# V7B_TI.net
KiCad netlist of a schematic drawn in EAGLE
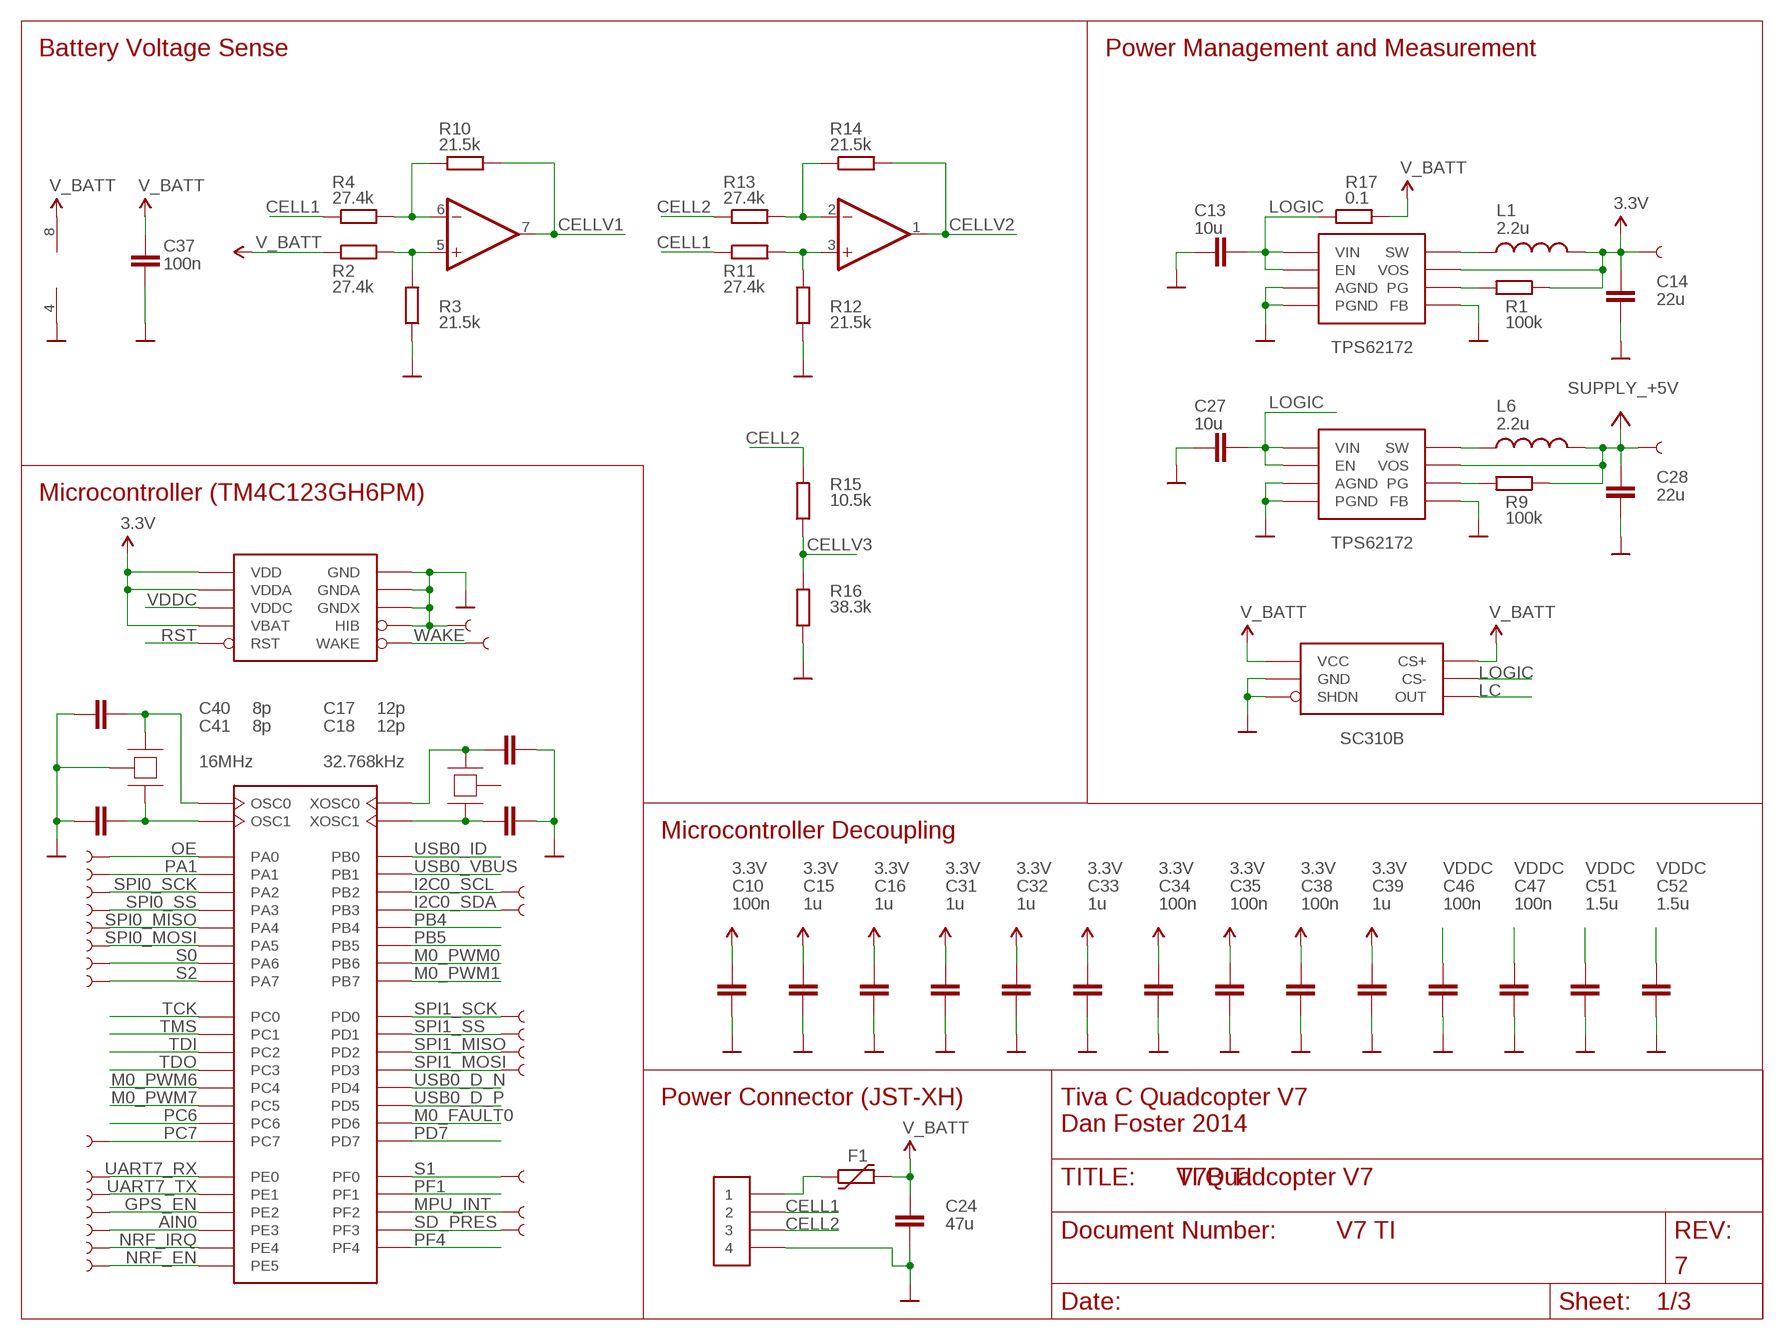
[diagram p0: schematic, sheet 1]
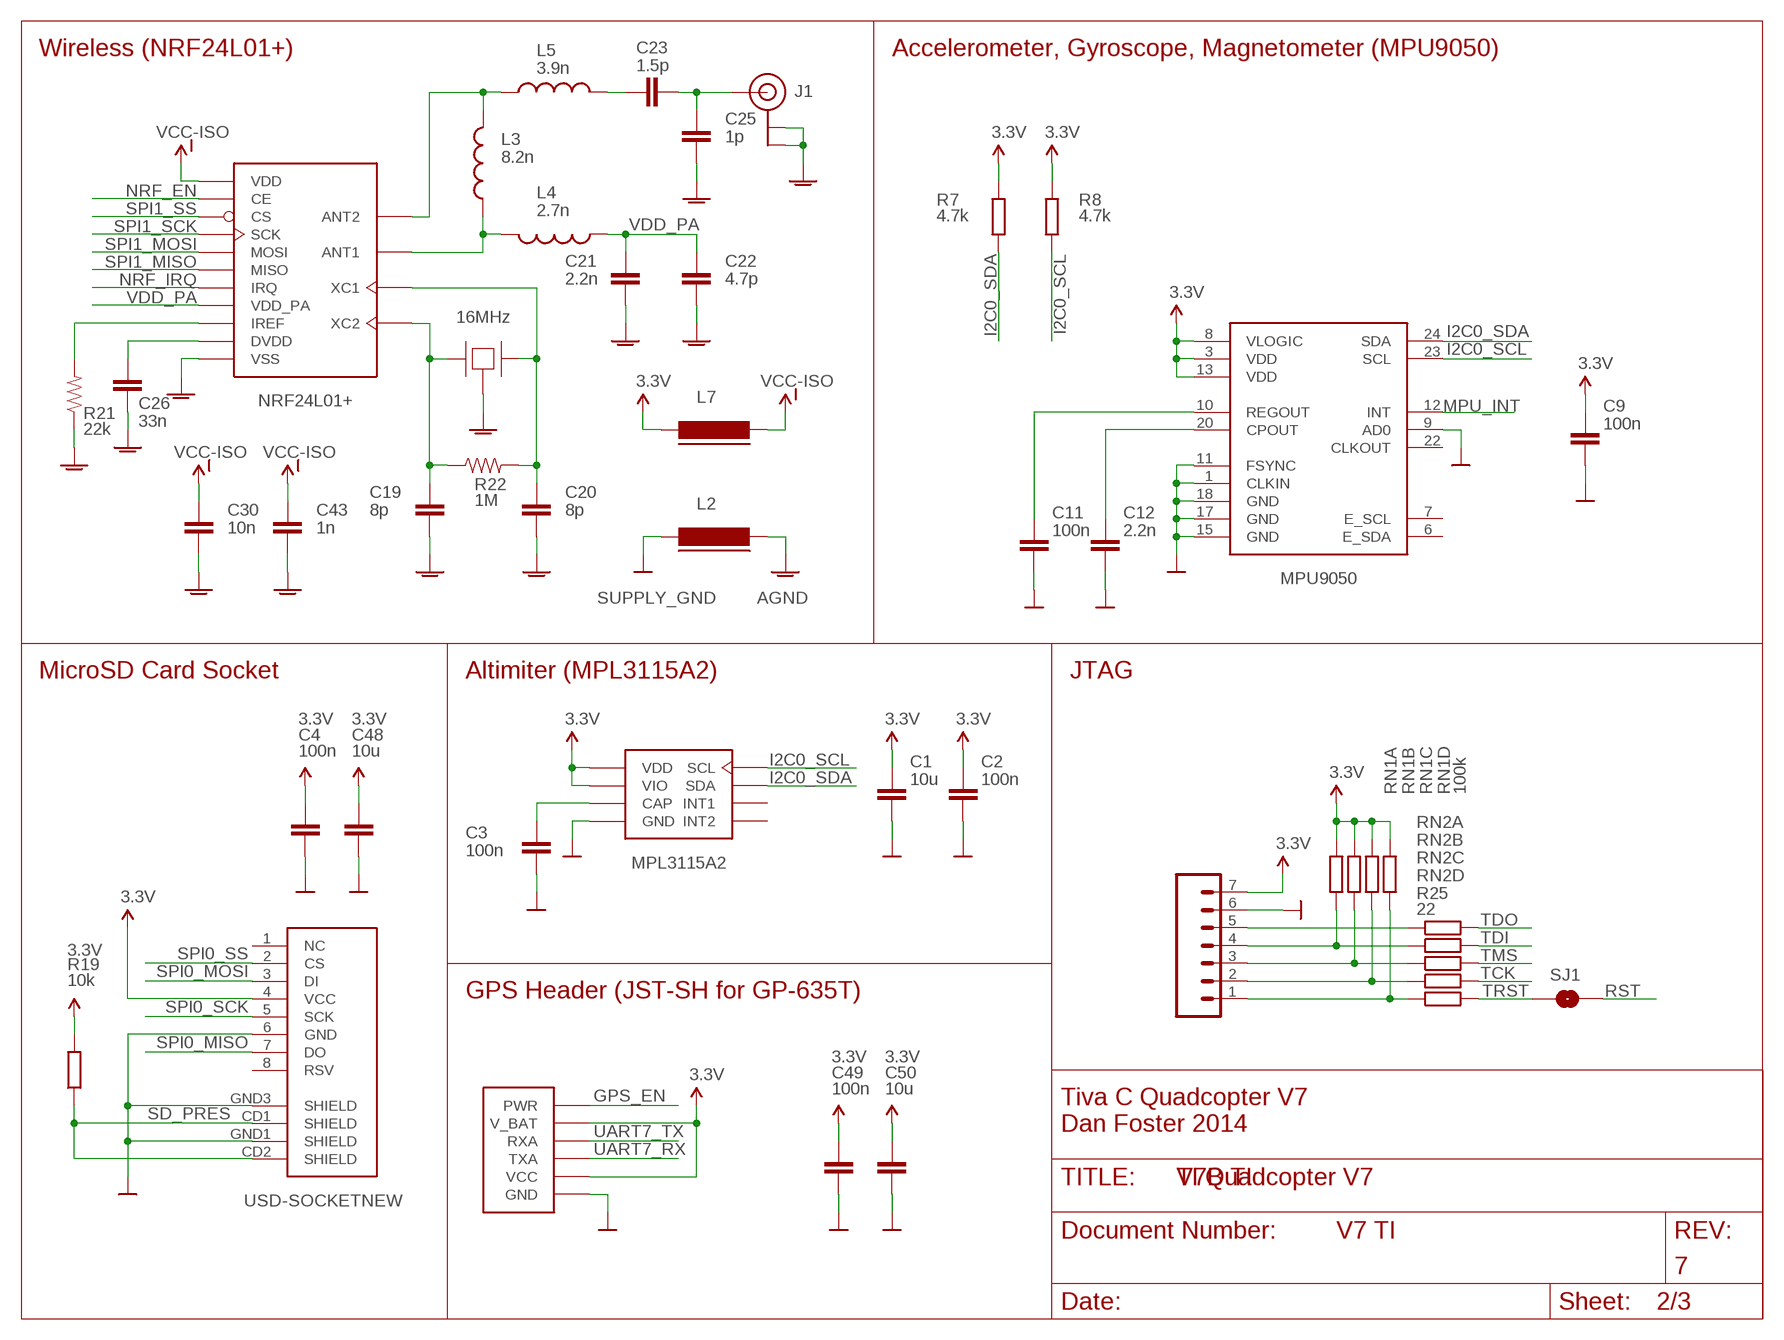
[diagram p1: schematic, sheet 2]
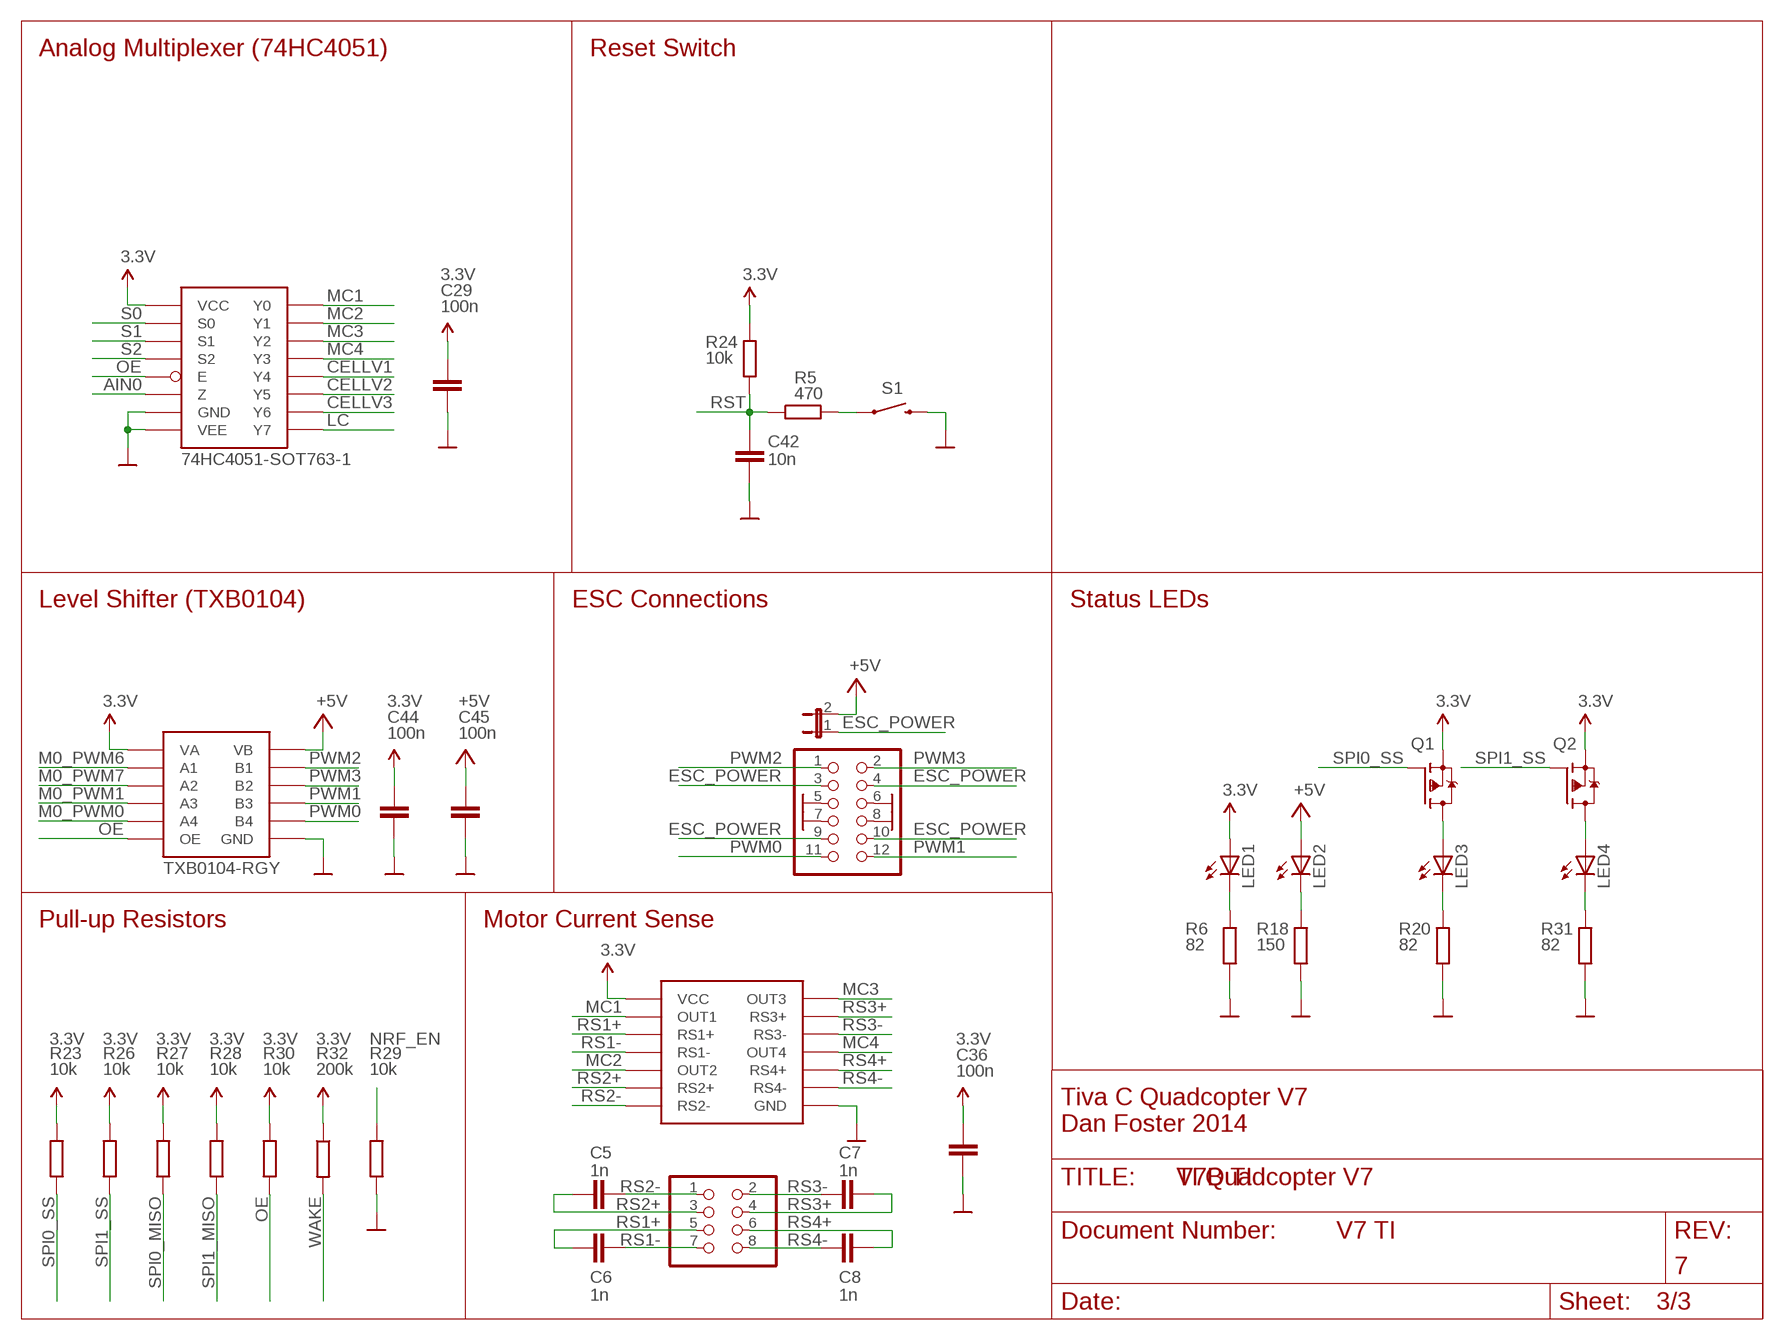
[diagram p2: schematic, sheet 3]

(export (version "E")
  (design (tool "Eeschema 10.0.6"))
  (components
    (comp (ref "C5")
      (value "1n")
      (footprint "eagle-import:C402")
      (libsource (lib "eagle-import") (part "CAPACITOR_NPOL-0402"))
    )
    (comp (ref "C6")
      (value "1n")
      (footprint "eagle-import:C402")
      (libsource (lib "eagle-import") (part "CAPACITOR_NPOL-0402"))
    )
    (comp (ref "C7")
      (value "1n")
      (footprint "eagle-import:C402")
      (libsource (lib "eagle-import") (part "CAPACITOR_NPOL-0402"))
    )
    (comp (ref "C8")
      (value "1n")
      (footprint "eagle-import:C402")
      (libsource (lib "eagle-import") (part "CAPACITOR_NPOL-0402"))
    )
    (comp (ref "C29")
      (value "100n")
      (footprint "eagle-import:C402")
      (libsource (lib "eagle-import") (part "CAPACITOR_NPOL-0402"))
    )
    (comp (ref "C36")
      (value "100n")
      (footprint "eagle-import:C402")
      (libsource (lib "eagle-import") (part "CAPACITOR_NPOL-0402"))
    )
    (comp (ref "C42")
      (value "10n")
      (footprint "eagle-import:C402")
      (libsource (lib "eagle-import") (part "CAPACITOR_NPOL-0402"))
    )
    (comp (ref "C44")
      (value "100n")
      (footprint "eagle-import:C402")
      (libsource (lib "eagle-import") (part "CAPACITOR_NPOL-0402"))
    )
    (comp (ref "C45")
      (value "100n")
      (footprint "eagle-import:C402")
      (libsource (lib "eagle-import") (part "CAPACITOR_NPOL-0402"))
    )
    (comp (ref "JP1")
      (value "PINHD-2X6")
      (footprint "eagle-import:2X06")
      (libsource (lib "eagle-import") (part "PINHD-2X6"))
    )
    (comp (ref "JP2")
      (value "PINHD-2X4")
      (footprint "eagle-import:2X04")
      (libsource (lib "eagle-import") (part "PINHD-2X4"))
    )
    (comp (ref "JP3")
      (value "JUMPER-2SMD-NO")
      (footprint "eagle-import:SJ_2S-NO")
      (libsource (lib "eagle-import") (part "JUMPER-2SMD-NO"))
    )
    (comp (ref "LED1")
      (value "LED-0603")
      (footprint "eagle-import:LED-603")
      (libsource (lib "eagle-import") (part "LED-0603"))
    )
    (comp (ref "LED2")
      (value "LED-0603")
      (footprint "eagle-import:LED-603")
      (libsource (lib "eagle-import") (part "LED-0603"))
    )
    (comp (ref "LED3")
      (value "LED-0603")
      (footprint "eagle-import:LED-603")
      (libsource (lib "eagle-import") (part "LED-0603"))
    )
    (comp (ref "LED4")
      (value "LED-0603")
      (footprint "eagle-import:LED-603")
      (libsource (lib "eagle-import") (part "LED-0603"))
    )
    (comp (ref "Q1")
      (value "BSS84CT-ND")
      (footprint "eagle-import:SOT-23")
      (libsource (lib "eagle-import") (part "TRANSISTOR_FET_TSM2301CX"))
    )
    (comp (ref "Q2")
      (value "BSS84CT-ND")
      (footprint "eagle-import:SOT-23")
      (libsource (lib "eagle-import") (part "TRANSISTOR_FET_TSM2301CX"))
    )
    (comp (ref "R5")
      (value "470")
      (footprint "eagle-import:R402")
      (libsource (lib "eagle-import") (part "RESISTOR-0402"))
    )
    (comp (ref "R6")
      (value "82")
      (footprint "eagle-import:R603")
      (libsource (lib "eagle-import") (part "RESISTOR-0603"))
    )
    (comp (ref "R18")
      (value "150")
      (footprint "eagle-import:R603")
      (libsource (lib "eagle-import") (part "RESISTOR-0603"))
    )
    (comp (ref "R20")
      (value "82")
      (footprint "eagle-import:R603")
      (libsource (lib "eagle-import") (part "RESISTOR-0603"))
    )
    (comp (ref "R23")
      (value "10k")
      (footprint "eagle-import:R402")
      (libsource (lib "eagle-import") (part "RESISTOR-0402"))
    )
    (comp (ref "R24")
      (value "10k")
      (footprint "eagle-import:R402")
      (libsource (lib "eagle-import") (part "RESISTOR-0402"))
    )
    (comp (ref "R26")
      (value "10k")
      (footprint "eagle-import:R402")
      (libsource (lib "eagle-import") (part "RESISTOR-0402"))
    )
    (comp (ref "R27")
      (value "10k")
      (footprint "eagle-import:R402")
      (libsource (lib "eagle-import") (part "RESISTOR-0402"))
    )
    (comp (ref "R28")
      (value "10k")
      (footprint "eagle-import:R402")
      (libsource (lib "eagle-import") (part "RESISTOR-0402"))
    )
    (comp (ref "R29")
      (value "10k")
      (footprint "eagle-import:R402")
      (libsource (lib "eagle-import") (part "RESISTOR-0402"))
    )
    (comp (ref "R30")
      (value "10k")
      (footprint "eagle-import:R402")
      (libsource (lib "eagle-import") (part "RESISTOR-0402"))
    )
    (comp (ref "R31")
      (value "82")
      (footprint "eagle-import:R603")
      (libsource (lib "eagle-import") (part "RESISTOR-0603"))
    )
    (comp (ref "R32")
      (value "200k")
      (footprint "eagle-import:R402")
      (libsource (lib "eagle-import") (part "RESISTOR-0402"))
    )
    (comp (ref "S1")
      (value "SWITCH-MOMENTARY-2SMD")
      (footprint "eagle-import:TACTILE_SWITCH_SMD")
      (libsource (lib "eagle-import") (part "SWITCH-MOMENTARY-2SMD"))
    )
    (comp (ref "U$1")
      (value "MAX4378XAUD+")
      (footprint "eagle-import:TSSOP-14")
      (libsource (lib "eagle-import") (part "MAX4378XAUD+"))
    )
    (comp (ref "U$8")
      (value "74HC4051")
      (footprint "eagle-import:NXP-SOT763-1")
      (libsource (lib "eagle-import") (part "74HC4051"))
    )
    (comp (ref "U$18")
      (value "TXB0104-RGY")
      (footprint "eagle-import:TI-RGY")
      (libsource (lib "eagle-import") (part "TXB0104-RGY"))
    )
    (comp (ref "C1")
      (value "10u")
      (footprint "eagle-import:C603")
      (libsource (lib "eagle-import") (part "CAPACITOR_NPOL-0603"))
    )
    (comp (ref "C2")
      (value "100n")
      (footprint "eagle-import:C402")
      (libsource (lib "eagle-import") (part "CAPACITOR_NPOL-0402"))
    )
    (comp (ref "C3")
      (value "100n")
      (footprint "eagle-import:C402")
      (libsource (lib "eagle-import") (part "CAPACITOR_NPOL-0402"))
    )
    (comp (ref "C4")
      (value "100n")
      (footprint "eagle-import:C402")
      (libsource (lib "eagle-import") (part "CAPACITOR_NPOL-0402"))
    )
    (comp (ref "C9")
      (value "100n")
      (footprint "eagle-import:C402")
      (libsource (lib "eagle-import") (part "CAPACITOR_NPOL-0402"))
    )
    (comp (ref "C11")
      (value "100n")
      (footprint "eagle-import:C402")
      (libsource (lib "eagle-import") (part "CAPACITOR_NPOL-0402"))
    )
    (comp (ref "C12")
      (value "2.2n")
      (footprint "eagle-import:C402")
      (libsource (lib "eagle-import") (part "CAPACITOR_NPOL-0402"))
    )
    (comp (ref "C19")
      (value "8p")
      (footprint "eagle-import:0402-CAP")
      (libsource (lib "eagle-import") (part "CAP0402-CAP"))
    )
    (comp (ref "C20")
      (value "8p")
      (footprint "eagle-import:0402-CAP")
      (libsource (lib "eagle-import") (part "CAP0402-CAP"))
    )
    (comp (ref "C21")
      (value "2.2n")
      (footprint "eagle-import:0402-CAP")
      (libsource (lib "eagle-import") (part "CAP0402-CAP"))
    )
    (comp (ref "C22")
      (value "4.7p")
      (footprint "eagle-import:0402-CAP")
      (libsource (lib "eagle-import") (part "CAP0402-CAP"))
    )
    (comp (ref "C23")
      (value "1.5p")
      (footprint "eagle-import:0402-CAP")
      (libsource (lib "eagle-import") (part "CAP0402-CAP"))
    )
    (comp (ref "C25")
      (value "1p")
      (footprint "eagle-import:0402-CAP")
      (libsource (lib "eagle-import") (part "CAP0402-CAP"))
    )
    (comp (ref "C26")
      (value "33n")
      (footprint "eagle-import:0402-CAP")
      (libsource (lib "eagle-import") (part "CAP0402-CAP"))
    )
    (comp (ref "C30")
      (value "10n")
      (footprint "eagle-import:0402-CAP")
      (libsource (lib "eagle-import") (part "CAP0402-CAP"))
    )
    (comp (ref "C43")
      (value "1n")
      (footprint "eagle-import:0402-CAP")
      (libsource (lib "eagle-import") (part "CAP0402-CAP"))
    )
    (comp (ref "C48")
      (value "10u")
      (footprint "eagle-import:C603")
      (libsource (lib "eagle-import") (part "CAPACITOR_NPOL-0603"))
    )
    (comp (ref "C49")
      (value "100n")
      (footprint "eagle-import:C402")
      (libsource (lib "eagle-import") (part "CAPACITOR_NPOL-0402"))
    )
    (comp (ref "C50")
      (value "10u")
      (footprint "eagle-import:C603")
      (libsource (lib "eagle-import") (part "CAPACITOR_NPOL-0603"))
    )
    (comp (ref "J1")
      (value "U.FL")
      (footprint "eagle-import:U.FL")
      (libsource (lib "eagle-import") (part "U.FL"))
    )
    (comp (ref "JP5")
      (value "M07")
      (footprint "eagle-import:1X07")
      (libsource (lib "eagle-import") (part "M07"))
    )
    (comp (ref "L2")
      (value "445-8677-1-ND")
      (footprint "eagle-import:FB603")
      (libsource (lib "eagle-import") (part "FERRITE-0603"))
    )
    (comp (ref "L3")
      (value "8.2n")
      (footprint "eagle-import:C0402")
      (libsource (lib "eagle-import") (part "INDUCTOR0402"))
    )
    (comp (ref "L4")
      (value "2.7n")
      (footprint "eagle-import:C0402")
      (libsource (lib "eagle-import") (part "INDUCTOR0402"))
    )
    (comp (ref "L5")
      (value "3.9n")
      (footprint "eagle-import:C0402")
      (libsource (lib "eagle-import") (part "INDUCTOR0402"))
    )
    (comp (ref "L7")
      (value "445-8677-1-ND")
      (footprint "eagle-import:FB603")
      (libsource (lib "eagle-import") (part "FERRITE-0603"))
    )
    (comp (ref "R7")
      (value "4.7k")
      (footprint "eagle-import:R402")
      (libsource (lib "eagle-import") (part "RESISTOR-0402"))
    )
    (comp (ref "R8")
      (value "4.7k")
      (footprint "eagle-import:R402")
      (libsource (lib "eagle-import") (part "RESISTOR-0402"))
    )
    (comp (ref "R19")
      (value "10k")
      (footprint "eagle-import:R402")
      (libsource (lib "eagle-import") (part "RESISTOR-0402"))
    )
    (comp (ref "R21")
      (value "22k")
      (footprint "eagle-import:0402-RES")
      (libsource (lib "eagle-import") (part "RESISTOR0402-RES"))
    )
    (comp (ref "R22")
      (value "1M")
      (footprint "eagle-import:0402-RES")
      (libsource (lib "eagle-import") (part "RESISTOR0402-RES"))
    )
    (comp (ref "R25")
      (value "22")
      (footprint "eagle-import:R402")
      (libsource (lib "eagle-import") (part "RESISTOR-0402"))
    )
    (comp (ref "RN1")
      (value "100k")
      (footprint "eagle-import:RN8P-4R-CRA06S")
      (libsource (lib "eagle-import") (part "RESISTOR_ARRAY_4"))
    )
    (comp (ref "RN2")
      (value "22")
      (footprint "eagle-import:RN8P-4R-CRA06S")
      (libsource (lib "eagle-import") (part "RESISTOR_ARRAY_4"))
    )
    (comp (ref "SJ1")
      (value "SOLDERJUMPERNO")
      (footprint "eagle-import:SJ_2S-NO")
      (libsource (lib "eagle-import") (part "SOLDERJUMPERNO"))
    )
    (comp (ref "U$3")
      (value "MPL3115A2")
      (footprint "eagle-import:MPLXXXXAX")
      (libsource (lib "eagle-import") (part "MPL3115A2"))
    )
    (comp (ref "U$10")
      (value "GPS-GP-635T-VERT")
      (footprint "eagle-import:JST-SH-6-SMD-T")
      (libsource (lib "eagle-import") (part "GPS-GP-635T-VERT"))
    )
    (comp (ref "U$11")
      (value "NRF24L01+")
      (footprint "eagle-import:QFN-20-4X4-0.5")
      (libsource (lib "eagle-import") (part "NRF24L01+"))
    )
    (comp (ref "U$13")
      (value "CRYSTAL-3.2X2.5")
      (footprint "eagle-import:TSX-3225")
      (libsource (lib "eagle-import") (part "CRYSTAL-3.2X2.5"))
    )
    (comp (ref "U1")
      (value "MPU9050")
      (footprint "eagle-import:QFN-24-NP")
      (libsource (lib "eagle-import") (part "MPU-9150QFN-24-NP"))
    )
    (comp (ref "U2")
      (value "USD-SOCKETNEW")
      (footprint "eagle-import:MICRO-SD-SOCKET-PP")
      (libsource (lib "eagle-import") (part "USD-SOCKETNEW"))
    )
    (comp (ref "C10")
      (value "100n")
      (footprint "eagle-import:C402")
      (libsource (lib "eagle-import") (part "CAPACITOR_NPOL-0402"))
    )
    (comp (ref "C13")
      (value "10u")
      (footprint "eagle-import:C805")
      (libsource (lib "eagle-import") (part "CAPACITOR_NPOL-0805"))
    )
    (comp (ref "C14")
      (value "22u")
      (footprint "eagle-import:C805")
      (libsource (lib "eagle-import") (part "CAPACITOR_NPOL-0805"))
    )
    (comp (ref "C15")
      (value "1u")
      (footprint "eagle-import:C402")
      (libsource (lib "eagle-import") (part "CAPACITOR_NPOL-0402"))
    )
    (comp (ref "C16")
      (value "1u")
      (footprint "eagle-import:C402")
      (libsource (lib "eagle-import") (part "CAPACITOR_NPOL-0402"))
    )
    (comp (ref "C17")
      (value "12p")
      (footprint "eagle-import:C402")
      (libsource (lib "eagle-import") (part "CAPACITOR_NPOL-0402"))
    )
    (comp (ref "C18")
      (value "12p")
      (footprint "eagle-import:C402")
      (libsource (lib "eagle-import") (part "CAPACITOR_NPOL-0402"))
    )
    (comp (ref "C24")
      (value "47u")
      (footprint "eagle-import:C1206")
      (libsource (lib "eagle-import") (part "CAPACITOR_NPOL-1206"))
    )
    (comp (ref "C27")
      (value "10u")
      (footprint "eagle-import:C805")
      (libsource (lib "eagle-import") (part "CAPACITOR_NPOL-0805"))
    )
    (comp (ref "C28")
      (value "22u")
      (footprint "eagle-import:C805")
      (libsource (lib "eagle-import") (part "CAPACITOR_NPOL-0805"))
    )
    (comp (ref "C31")
      (value "1u")
      (footprint "eagle-import:C402")
      (libsource (lib "eagle-import") (part "CAPACITOR_NPOL-0402"))
    )
    (comp (ref "C32")
      (value "1u")
      (footprint "eagle-import:C402")
      (libsource (lib "eagle-import") (part "CAPACITOR_NPOL-0402"))
    )
    (comp (ref "C33")
      (value "1u")
      (footprint "eagle-import:C402")
      (libsource (lib "eagle-import") (part "CAPACITOR_NPOL-0402"))
    )
    (comp (ref "C34")
      (value "100n")
      (footprint "eagle-import:C402")
      (libsource (lib "eagle-import") (part "CAPACITOR_NPOL-0402"))
    )
    (comp (ref "C35")
      (value "100n")
      (footprint "eagle-import:C402")
      (libsource (lib "eagle-import") (part "CAPACITOR_NPOL-0402"))
    )
    (comp (ref "C37")
      (value "100n")
      (footprint "eagle-import:C402")
      (libsource (lib "eagle-import") (part "CAPACITOR_NPOL-0402"))
    )
    (comp (ref "C38")
      (value "100n")
      (footprint "eagle-import:C402")
      (libsource (lib "eagle-import") (part "CAPACITOR_NPOL-0402"))
    )
    (comp (ref "C39")
      (value "1u")
      (footprint "eagle-import:C402")
      (libsource (lib "eagle-import") (part "CAPACITOR_NPOL-0402"))
    )
    (comp (ref "C40")
      (value "8p")
      (footprint "eagle-import:C402")
      (libsource (lib "eagle-import") (part "CAPACITOR_NPOL-0402"))
    )
    (comp (ref "C41")
      (value "8p")
      (footprint "eagle-import:C402")
      (libsource (lib "eagle-import") (part "CAPACITOR_NPOL-0402"))
    )
    (comp (ref "C46")
      (value "100n")
      (footprint "eagle-import:C402")
      (libsource (lib "eagle-import") (part "CAPACITOR_NPOL-0402"))
    )
    (comp (ref "C47")
      (value "100n")
      (footprint "eagle-import:C402")
      (libsource (lib "eagle-import") (part "CAPACITOR_NPOL-0402"))
    )
    (comp (ref "C51")
      (value "1.5u")
      (footprint "eagle-import:C402")
      (libsource (lib "eagle-import") (part "CAPACITOR_NPOL-0402"))
    )
    (comp (ref "C52")
      (value "1.5u")
      (footprint "eagle-import:C402")
      (libsource (lib "eagle-import") (part "CAPACITOR_NPOL-0402"))
    )
    (comp (ref "F1")
      (value "FUSE_PTC-1812")
      (footprint "eagle-import:PTC1812L")
      (libsource (lib "eagle-import") (part "FUSE_PTC-1812"))
    )
    (comp (ref "IC2")
      (value "OPA2743EA")
      (footprint "eagle-import:MSOP08")
      (libsource (lib "eagle-import") (part "OPA2743EA"))
    )
    (comp (ref "L1")
      (value "2.2u")
      (footprint "eagle-import:1210")
      (libsource (lib "eagle-import") (part "INDUCTOR1210"))
    )
    (comp (ref "L6")
      (value "2.2u")
      (footprint "eagle-import:1210")
      (libsource (lib "eagle-import") (part "INDUCTOR1210"))
    )
    (comp (ref "R1")
      (value "100k")
      (footprint "eagle-import:R402")
      (libsource (lib "eagle-import") (part "RESISTOR-0402"))
    )
    (comp (ref "R2")
      (value "27.4k")
      (footprint "eagle-import:R402")
      (libsource (lib "eagle-import") (part "RESISTOR-0402"))
    )
    (comp (ref "R3")
      (value "21.5k")
      (footprint "eagle-import:R402")
      (libsource (lib "eagle-import") (part "RESISTOR-0402"))
    )
    (comp (ref "R4")
      (value "27.4k")
      (footprint "eagle-import:R402")
      (libsource (lib "eagle-import") (part "RESISTOR-0402"))
    )
    (comp (ref "R9")
      (value "100k")
      (footprint "eagle-import:R402")
      (libsource (lib "eagle-import") (part "RESISTOR-0402"))
    )
    (comp (ref "R10")
      (value "21.5k")
      (footprint "eagle-import:R402")
      (libsource (lib "eagle-import") (part "RESISTOR-0402"))
    )
    (comp (ref "R11")
      (value "27.4k")
      (footprint "eagle-import:R402")
      (libsource (lib "eagle-import") (part "RESISTOR-0402"))
    )
    (comp (ref "R12")
      (value "21.5k")
      (footprint "eagle-import:R402")
      (libsource (lib "eagle-import") (part "RESISTOR-0402"))
    )
    (comp (ref "R13")
      (value "27.4k")
      (footprint "eagle-import:R402")
      (libsource (lib "eagle-import") (part "RESISTOR-0402"))
    )
    (comp (ref "R14")
      (value "21.5k")
      (footprint "eagle-import:R402")
      (libsource (lib "eagle-import") (part "RESISTOR-0402"))
    )
    (comp (ref "R15")
      (value "10.5k")
      (footprint "eagle-import:R402")
      (libsource (lib "eagle-import") (part "RESISTOR-0402"))
    )
    (comp (ref "R16")
      (value "38.3k")
      (footprint "eagle-import:R402")
      (libsource (lib "eagle-import") (part "RESISTOR-0402"))
    )
    (comp (ref "R17")
      (value "0.1")
      (footprint "eagle-import:R1206")
      (libsource (lib "eagle-import") (part "RESISTOR-1206"))
    )
    (comp (ref "TP1")
      (value "TEST-POINT3")
      (footprint "eagle-import:PAD.03X.03")
      (libsource (lib "eagle-import") (part "TEST-POINT3"))
    )
    (comp (ref "TP2")
      (value "TEST-POINT3")
      (footprint "eagle-import:PAD.03X.03")
      (libsource (lib "eagle-import") (part "TEST-POINT3"))
    )
    (comp (ref "TP3")
      (value "TEST-POINT3")
      (footprint "eagle-import:PAD.03X.03")
      (libsource (lib "eagle-import") (part "TEST-POINT3"))
    )
    (comp (ref "TP4")
      (value "TEST-POINT3")
      (footprint "eagle-import:PAD.03X.03")
      (libsource (lib "eagle-import") (part "TEST-POINT3"))
    )
    (comp (ref "TP5")
      (value "TEST-POINT3")
      (footprint "eagle-import:PAD.03X.03")
      (libsource (lib "eagle-import") (part "TEST-POINT3"))
    )
    (comp (ref "TP6")
      (value "TEST-POINT3")
      (footprint "eagle-import:PAD.03X.03")
      (libsource (lib "eagle-import") (part "TEST-POINT3"))
    )
    (comp (ref "TP7")
      (value "TEST-POINT3")
      (footprint "eagle-import:PAD.03X.03")
      (libsource (lib "eagle-import") (part "TEST-POINT3"))
    )
    (comp (ref "TP8")
      (value "TEST-POINT3")
      (footprint "eagle-import:PAD.03X.03")
      (libsource (lib "eagle-import") (part "TEST-POINT3"))
    )
    (comp (ref "TP9")
      (value "TEST-POINT3")
      (footprint "eagle-import:PAD.03X.03")
      (libsource (lib "eagle-import") (part "TEST-POINT3"))
    )
    (comp (ref "TP10")
      (value "TEST-POINT3")
      (footprint "eagle-import:PAD.03X.03")
      (libsource (lib "eagle-import") (part "TEST-POINT3"))
    )
    (comp (ref "TP11")
      (value "TEST-POINT3")
      (footprint "eagle-import:PAD.03X.03")
      (libsource (lib "eagle-import") (part "TEST-POINT3"))
    )
    (comp (ref "TP12")
      (value "TEST-POINT3")
      (footprint "eagle-import:PAD.03X.03")
      (libsource (lib "eagle-import") (part "TEST-POINT3"))
    )
    (comp (ref "TP13")
      (value "TEST-POINT3")
      (footprint "eagle-import:PAD.03X.03")
      (libsource (lib "eagle-import") (part "TEST-POINT3"))
    )
    (comp (ref "TP14")
      (value "TEST-POINT3")
      (footprint "eagle-import:PAD.03X.03")
      (libsource (lib "eagle-import") (part "TEST-POINT3"))
    )
    (comp (ref "TP15")
      (value "TEST-POINT3")
      (footprint "eagle-import:PAD.03X.03")
      (libsource (lib "eagle-import") (part "TEST-POINT3"))
    )
    (comp (ref "TP16")
      (value "TEST-POINT3")
      (footprint "eagle-import:PAD.03X.03")
      (libsource (lib "eagle-import") (part "TEST-POINT3"))
    )
    (comp (ref "TP17")
      (value "TEST-POINT3")
      (footprint "eagle-import:PAD.03X.03")
      (libsource (lib "eagle-import") (part "TEST-POINT3"))
    )
    (comp (ref "TP18")
      (value "TEST-POINT3")
      (footprint "eagle-import:PAD.03X.03")
      (libsource (lib "eagle-import") (part "TEST-POINT3"))
    )
    (comp (ref "TP19")
      (value "TEST-POINT3")
      (footprint "eagle-import:PAD.03X.03")
      (libsource (lib "eagle-import") (part "TEST-POINT3"))
    )
    (comp (ref "TP20")
      (value "TEST-POINT3")
      (footprint "eagle-import:PAD.03X.03")
      (libsource (lib "eagle-import") (part "TEST-POINT3"))
    )
    (comp (ref "TP21")
      (value "TEST-POINT3")
      (footprint "eagle-import:PAD.03X.03")
      (libsource (lib "eagle-import") (part "TEST-POINT3"))
    )
    (comp (ref "TP22")
      (value "TEST-POINT3")
      (footprint "eagle-import:PAD.03X.03")
      (libsource (lib "eagle-import") (part "TEST-POINT3"))
    )
    (comp (ref "TP23")
      (value "TEST-POINT3")
      (footprint "eagle-import:PAD.03X.03")
      (libsource (lib "eagle-import") (part "TEST-POINT3"))
    )
    (comp (ref "TP24")
      (value "TEST-POINT3")
      (footprint "eagle-import:PAD.03X.03")
      (libsource (lib "eagle-import") (part "TEST-POINT3"))
    )
    (comp (ref "TP25")
      (value "TEST-POINT3")
      (footprint "eagle-import:PAD.03X.03")
      (libsource (lib "eagle-import") (part "TEST-POINT3"))
    )
    (comp (ref "TP26")
      (value "TEST-POINT3")
      (footprint "eagle-import:PAD.03X.03")
      (libsource (lib "eagle-import") (part "TEST-POINT3"))
    )
    (comp (ref "TP27")
      (value "TEST-POINT3")
      (footprint "eagle-import:PAD.03X.03")
      (libsource (lib "eagle-import") (part "TEST-POINT3"))
    )
    (comp (ref "TP29")
      (value "TEST-POINT3")
      (footprint "eagle-import:PAD.03X.03")
      (libsource (lib "eagle-import") (part "TEST-POINT3"))
    )
    (comp (ref "U$2")
      (value "TPS62172")
      (footprint "eagle-import:S-PWSON-N8")
      (libsource (lib "eagle-import") (part "TPS62172"))
    )
    (comp (ref "U$4")
      (value "TPS62172")
      (footprint "eagle-import:S-PWSON-N8")
      (libsource (lib "eagle-import") (part "TPS62172"))
    )
    (comp (ref "U$5")
      (value "TM4C123GH6PM")
      (footprint "eagle-import:TI-PM")
      (libsource (lib "eagle-import") (part "TM4C123GH6PM"))
    )
    (comp (ref "U$6")
      (value "JST-XH-4-SMD")
      (footprint "eagle-import:JST-XH-4-SMD")
      (libsource (lib "eagle-import") (part "JST-XH-4-SMD"))
    )
    (comp (ref "U$7")
      (value "CRYSTAL-3.2X2.5")
      (footprint "eagle-import:TSX-3225")
      (libsource (lib "eagle-import") (part "CRYSTAL-3.2X2.5"))
    )
    (comp (ref "U$9")
      (value "SC130")
      (footprint "eagle-import:SOT-23-6")
      (libsource (lib "eagle-import") (part "SC130"))
    )
    (comp (ref "U$12")
      (value "CRYSTAL-WATCH-SMD")
      (footprint "eagle-import:CRYSTAL-WATCH-SMD")
      (libsource (lib "eagle-import") (part "CRYSTAL-WATCH-SMD"))
    )
  )
  (nets
    (net (code "1") (name "+5V") (class "Default")
      (node (ref "C28") (pin "2") (pinfunction "2_2") (pintype "passive"))
      (node (ref "C45") (pin "1") (pinfunction "1_1") (pintype "passive"))
      (node (ref "JP3") (pin "2") (pinfunction "2_2") (pintype "passive"))
      (node (ref "L6") (pin "2") (pinfunction "2_2") (pintype "passive"))
      (node (ref "LED2") (pin "A") (pinfunction "A_A") (pintype "passive"))
      (node (ref "R9") (pin "1") (pinfunction "1_1") (pintype "passive"))
      (node (ref "TP14") (pin "P$1") (pinfunction "1_P$1") (pintype "bidirectional"))
      (node (ref "U$18") (pin "14") (pinfunction "VB_14") (pintype "power_in"))
      (node (ref "U$4") (pin "6") (pinfunction "VOS_6") (pintype "input"))
    )
    (net (code "2") (name "3.3V") (class "Default")
      (node (ref "C1") (pin "1") (pinfunction "1_1") (pintype "passive"))
      (node (ref "C10") (pin "1") (pinfunction "1_1") (pintype "passive"))
      (node (ref "C14") (pin "2") (pinfunction "2_2") (pintype "passive"))
      (node (ref "C15") (pin "1") (pinfunction "1_1") (pintype "passive"))
      (node (ref "C16") (pin "1") (pinfunction "1_1") (pintype "passive"))
      (node (ref "C2") (pin "1") (pinfunction "1_1") (pintype "passive"))
      (node (ref "C29") (pin "1") (pinfunction "1_1") (pintype "passive"))
      (node (ref "C31") (pin "1") (pinfunction "1_1") (pintype "passive"))
      (node (ref "C32") (pin "1") (pinfunction "1_1") (pintype "passive"))
      (node (ref "C33") (pin "1") (pinfunction "1_1") (pintype "passive"))
      (node (ref "C34") (pin "1") (pinfunction "1_1") (pintype "passive"))
      (node (ref "C35") (pin "1") (pinfunction "1_1") (pintype "passive"))
      (node (ref "C36") (pin "1") (pinfunction "1_1") (pintype "passive"))
      (node (ref "C38") (pin "1") (pinfunction "1_1") (pintype "passive"))
      (node (ref "C39") (pin "1") (pinfunction "1_1") (pintype "passive"))
      (node (ref "C4") (pin "1") (pinfunction "1_1") (pintype "passive"))
      (node (ref "C44") (pin "1") (pinfunction "1_1") (pintype "passive"))
      (node (ref "C48") (pin "1") (pinfunction "1_1") (pintype "passive"))
      (node (ref "C49") (pin "1") (pinfunction "1_1") (pintype "passive"))
      (node (ref "C50") (pin "1") (pinfunction "1_1") (pintype "passive"))
      (node (ref "C9") (pin "1") (pinfunction "1_1") (pintype "passive"))
      (node (ref "JP5") (pin "7") (pinfunction "7_7") (pintype "passive"))
      (node (ref "L1") (pin "2") (pinfunction "2_2") (pintype "passive"))
      (node (ref "L7") (pin "1") (pinfunction "1_1") (pintype "passive"))
      (node (ref "LED1") (pin "A") (pinfunction "A_A") (pintype "passive"))
      (node (ref "Q1") (pin "2") (pinfunction "S_2") (pintype "passive"))
      (node (ref "Q2") (pin "2") (pinfunction "S_2") (pintype "passive"))
      (node (ref "R1") (pin "1") (pinfunction "1_1") (pintype "passive"))
      (node (ref "R19") (pin "2") (pinfunction "2_2") (pintype "passive"))
      (node (ref "R23") (pin "2") (pinfunction "2_2") (pintype "passive"))
      (node (ref "R24") (pin "2") (pinfunction "2_2") (pintype "passive"))
      (node (ref "R26") (pin "2") (pinfunction "2_2") (pintype "passive"))
      (node (ref "R27") (pin "2") (pinfunction "2_2") (pintype "passive"))
      (node (ref "R28") (pin "2") (pinfunction "2_2") (pintype "passive"))
      (node (ref "R30") (pin "2") (pinfunction "2_2") (pintype "passive"))
      (node (ref "R32") (pin "1") (pinfunction "1_1") (pintype "passive"))
      (node (ref "R7") (pin "1") (pinfunction "1_1") (pintype "passive"))
      (node (ref "R8") (pin "1") (pinfunction "1_1") (pintype "passive"))
      (node (ref "RN1") (pin "5") (pinfunction "2_5") (pintype "passive"))
      (node (ref "RN1") (pin "6") (pinfunction "2_6") (pintype "passive"))
      (node (ref "RN1") (pin "7") (pinfunction "2_7") (pintype "passive"))
      (node (ref "RN1") (pin "8") (pinfunction "2_8") (pintype "passive"))
      (node (ref "TP15") (pin "P$1") (pinfunction "1_P$1") (pintype "bidirectional"))
      (node (ref "U$1") (pin "P$4") (pinfunction "VCC_P$4") (pintype "power_in"))
      (node (ref "U$10") (pin "2") (pinfunction "VCC_2") (pintype "power_in"))
      (node (ref "U$10") (pin "5") (pinfunction "V_BAT_5") (pintype "input"))
      (node (ref "U$18") (pin "1") (pinfunction "VA_1") (pintype "power_in"))
      (node (ref "U$2") (pin "6") (pinfunction "VOS_6") (pintype "input"))
      (node (ref "U$3") (pin "1") (pinfunction "VDD_1") (pintype "power_in"))
      (node (ref "U$3") (pin "4") (pinfunction "VIO_4") (pintype "power_in"))
      (node (ref "U$5") (pin "P$11") (pinfunction "VDD_P$11") (pintype "power_in"))
      (node (ref "U$5") (pin "P$2") (pinfunction "VDDA_P$2") (pintype "power_in"))
      (node (ref "U$5") (pin "P$26") (pinfunction "VDD_P$26") (pintype "power_in"))
      (node (ref "U$5") (pin "P$37") (pinfunction "VBAT_P$37") (pintype "power_in"))
      (node (ref "U$5") (pin "P$42") (pinfunction "VDD_P$42") (pintype "power_in"))
      (node (ref "U$5") (pin "P$54") (pinfunction "VDD_P$54") (pintype "power_in"))
      (node (ref "U$8") (pin "16") (pinfunction "VCC_16") (pintype "power_in"))
      (node (ref "U$8") (pin "PAD") (pinfunction "VCC_PAD") (pintype "power_in"))
      (node (ref "U1") (pin "13") (pinfunction "VDD_13") (pintype "bidirectional"))
      (node (ref "U1") (pin "3") (pinfunction "VDD_3") (pintype "bidirectional"))
      (node (ref "U1") (pin "8") (pinfunction "VLOGIC_8") (pintype "bidirectional"))
      (node (ref "U2") (pin "4") (pinfunction "VCC_4") (pintype "bidirectional"))
    )
    (net (code "3") (name "AGND") (class "Default")
      (node (ref "C19") (pin "2") (pinfunction "2_2") (pintype "passive"))
      (node (ref "C20") (pin "2") (pinfunction "2_2") (pintype "passive"))
      (node (ref "C21") (pin "2") (pinfunction "2_2") (pintype "passive"))
      (node (ref "C22") (pin "2") (pinfunction "2_2") (pintype "passive"))
      (node (ref "C25") (pin "2") (pinfunction "2_2") (pintype "passive"))
      (node (ref "C26") (pin "2") (pinfunction "2_2") (pintype "passive"))
      (node (ref "C30") (pin "2") (pinfunction "2_2") (pintype "passive"))
      (node (ref "C43") (pin "2") (pinfunction "2_2") (pintype "passive"))
      (node (ref "J1") (pin "P$1") (pinfunction "GND_P$1") (pintype "bidirectional"))
      (node (ref "J1") (pin "P$2") (pinfunction "GND_P$2") (pintype "bidirectional"))
      (node (ref "L2") (pin "2") (pinfunction "2_2") (pintype "passive"))
      (node (ref "R21") (pin "1") (pinfunction "1_1") (pintype "passive"))
      (node (ref "U$11") (pin "P$14") (pinfunction "VSS_P$14") (pintype "power_in"))
      (node (ref "U$11") (pin "P$17") (pinfunction "VSS_P$17") (pintype "power_in"))
      (node (ref "U$11") (pin "P$20") (pinfunction "VSS_P$20") (pintype "power_in"))
      (node (ref "U$11") (pin "P$8") (pinfunction "VSS_P$8") (pintype "power_in"))
      (node (ref "U$13") (pin "G1") (pinfunction "CASE_G1") (pintype "power_in"))
      (node (ref "U$13") (pin "G2") (pinfunction "CASE_G2") (pintype "power_in"))
    )
    (net (code "4") (name "AIN0") (class "Default")
      (node (ref "TP11") (pin "P$1") (pinfunction "1_P$1") (pintype "bidirectional"))
      (node (ref "U$5") (pin "P$6") (pinfunction "PE3_P$6") (pintype "bidirectional"))
      (node (ref "U$8") (pin "3") (pinfunction "Z_3") (pintype "bidirectional"))
    )
    (net (code "5") (name "CASE") (class "Default")
      (node (ref "U$12") (pin "BODY") (pinfunction "CASE_BODY") (pintype "power_in"))
    )
    (net (code "6") (name "CELL1") (class "Default")
      (node (ref "R11") (pin "1") (pinfunction "1_1") (pintype "passive"))
      (node (ref "R4") (pin "1") (pinfunction "1_1") (pintype "passive"))
      (node (ref "U$6") (pin "2") (pinfunction "2_2") (pintype "bidirectional"))
    )
    (net (code "7") (name "CELL2") (class "Default")
      (node (ref "R13") (pin "1") (pinfunction "1_1") (pintype "passive"))
      (node (ref "R15") (pin "2") (pinfunction "2_2") (pintype "passive"))
      (node (ref "U$6") (pin "3") (pinfunction "3_3") (pintype "bidirectional"))
    )
    (net (code "8") (name "CELLV1") (class "Default")
      (node (ref "IC2") (pin "7") (pinfunction "OUT_7") (pintype "output"))
      (node (ref "R10") (pin "2") (pinfunction "2_2") (pintype "passive"))
      (node (ref "U$8") (pin "1") (pinfunction "Y4_1") (pintype "bidirectional"))
    )
    (net (code "9") (name "CELLV2") (class "Default")
      (node (ref "IC2") (pin "1") (pinfunction "OUT_1") (pintype "output"))
      (node (ref "R14") (pin "2") (pinfunction "2_2") (pintype "passive"))
      (node (ref "U$8") (pin "5") (pinfunction "Y5_5") (pintype "bidirectional"))
    )
    (net (code "10") (name "CELLV3") (class "Default")
      (node (ref "R15") (pin "1") (pinfunction "1_1") (pintype "passive"))
      (node (ref "R16") (pin "2") (pinfunction "2_2") (pintype "passive"))
      (node (ref "U$8") (pin "2") (pinfunction "Y6_2") (pintype "bidirectional"))
    )
    (net (code "11") (name "ESC_POWER") (class "Default")
      (node (ref "JP1") (pin "10") (pinfunction "10_10") (pintype "passive"))
      (node (ref "JP1") (pin "3") (pinfunction "3_3") (pintype "passive"))
      (node (ref "JP1") (pin "4") (pinfunction "4_4") (pintype "passive"))
      (node (ref "JP1") (pin "9") (pinfunction "9_9") (pintype "passive"))
      (node (ref "JP3") (pin "1") (pinfunction "1_1") (pintype "passive"))
    )
    (net (code "12") (name "GND") (class "Default")
      (node (ref "C1") (pin "2") (pinfunction "2_2") (pintype "passive"))
      (node (ref "C10") (pin "2") (pinfunction "2_2") (pintype "passive"))
      (node (ref "C11") (pin "2") (pinfunction "2_2") (pintype "passive"))
      (node (ref "C12") (pin "2") (pinfunction "2_2") (pintype "passive"))
      (node (ref "C13") (pin "2") (pinfunction "2_2") (pintype "passive"))
      (node (ref "C14") (pin "1") (pinfunction "1_1") (pintype "passive"))
      (node (ref "C15") (pin "2") (pinfunction "2_2") (pintype "passive"))
      (node (ref "C16") (pin "2") (pinfunction "2_2") (pintype "passive"))
      (node (ref "C17") (pin "2") (pinfunction "2_2") (pintype "passive"))
      (node (ref "C18") (pin "2") (pinfunction "2_2") (pintype "passive"))
      (node (ref "C2") (pin "2") (pinfunction "2_2") (pintype "passive"))
      (node (ref "C24") (pin "2") (pinfunction "2_2") (pintype "passive"))
      (node (ref "C27") (pin "2") (pinfunction "2_2") (pintype "passive"))
      (node (ref "C28") (pin "1") (pinfunction "1_1") (pintype "passive"))
      (node (ref "C29") (pin "2") (pinfunction "2_2") (pintype "passive"))
      (node (ref "C3") (pin "2") (pinfunction "2_2") (pintype "passive"))
      (node (ref "C31") (pin "2") (pinfunction "2_2") (pintype "passive"))
      (node (ref "C32") (pin "2") (pinfunction "2_2") (pintype "passive"))
      (node (ref "C33") (pin "2") (pinfunction "2_2") (pintype "passive"))
      (node (ref "C34") (pin "2") (pinfunction "2_2") (pintype "passive"))
      (node (ref "C35") (pin "2") (pinfunction "2_2") (pintype "passive"))
      (node (ref "C36") (pin "2") (pinfunction "2_2") (pintype "passive"))
      (node (ref "C37") (pin "2") (pinfunction "2_2") (pintype "passive"))
      (node (ref "C38") (pin "2") (pinfunction "2_2") (pintype "passive"))
      (node (ref "C39") (pin "2") (pinfunction "2_2") (pintype "passive"))
      (node (ref "C4") (pin "2") (pinfunction "2_2") (pintype "passive"))
      (node (ref "C40") (pin "1") (pinfunction "1_1") (pintype "passive"))
      (node (ref "C41") (pin "1") (pinfunction "1_1") (pintype "passive"))
      (node (ref "C42") (pin "2") (pinfunction "2_2") (pintype "passive"))
      (node (ref "C44") (pin "2") (pinfunction "2_2") (pintype "passive"))
      (node (ref "C45") (pin "2") (pinfunction "2_2") (pintype "passive"))
      (node (ref "C46") (pin "2") (pinfunction "2_2") (pintype "passive"))
      (node (ref "C47") (pin "2") (pinfunction "2_2") (pintype "passive"))
      (node (ref "C48") (pin "2") (pinfunction "2_2") (pintype "passive"))
      (node (ref "C49") (pin "2") (pinfunction "2_2") (pintype "passive"))
      (node (ref "C50") (pin "2") (pinfunction "2_2") (pintype "passive"))
      (node (ref "C51") (pin "2") (pinfunction "2_2") (pintype "passive"))
      (node (ref "C52") (pin "2") (pinfunction "2_2") (pintype "passive"))
      (node (ref "C9") (pin "2") (pinfunction "2_2") (pintype "passive"))
      (node (ref "IC2") (pin "4") (pinfunction "V-_4") (pintype "power_in"))
      (node (ref "JP1") (pin "5") (pinfunction "5_5") (pintype "passive"))
      (node (ref "JP1") (pin "6") (pinfunction "6_6") (pintype "passive"))
      (node (ref "JP1") (pin "7") (pinfunction "7_7") (pintype "passive"))
      (node (ref "JP1") (pin "8") (pinfunction "8_8") (pintype "passive"))
      (node (ref "JP5") (pin "6") (pinfunction "6_6") (pintype "passive"))
      (node (ref "L2") (pin "1") (pinfunction "1_1") (pintype "passive"))
      (node (ref "R12") (pin "1") (pinfunction "1_1") (pintype "passive"))
      (node (ref "R16") (pin "1") (pinfunction "1_1") (pintype "passive"))
      (node (ref "R18") (pin "2") (pinfunction "2_2") (pintype "passive"))
      (node (ref "R20") (pin "2") (pinfunction "2_2") (pintype "passive"))
      (node (ref "R29") (pin "1") (pinfunction "1_1") (pintype "passive"))
      (node (ref "R3") (pin "1") (pinfunction "1_1") (pintype "passive"))
      (node (ref "R31") (pin "2") (pinfunction "2_2") (pintype "passive"))
      (node (ref "R6") (pin "2") (pinfunction "2_2") (pintype "passive"))
      (node (ref "S1") (pin "3") (pinfunction "2_3") (pintype "passive"))
      (node (ref "TP16") (pin "P$1") (pinfunction "1_P$1") (pintype "bidirectional"))
      (node (ref "U$1") (pin "P$11") (pinfunction "GND_P$11") (pintype "power_in"))
      (node (ref "U$10") (pin "1") (pinfunction "GND_1") (pintype "power_in"))
      (node (ref "U$18") (pin "7") (pinfunction "GND_7") (pintype "power_in"))
      (node (ref "U$18") (pin "PAD") (pinfunction "GND_PAD") (pintype "power_in"))
      (node (ref "U$18") (pin "V1") (pinfunction "GND_V1") (pintype "power_in"))
      (node (ref "U$18") (pin "V2") (pinfunction "GND_V2") (pintype "power_in"))
      (node (ref "U$18") (pin "V3") (pinfunction "GND_V3") (pintype "power_in"))
      (node (ref "U$18") (pin "V4") (pinfunction "GND_V4") (pintype "power_in"))
      (node (ref "U$2") (pin "1") (pinfunction "PGND_1") (pintype "power_in"))
      (node (ref "U$2") (pin "4") (pinfunction "AGND_4") (pintype "power_in"))
      (node (ref "U$2") (pin "5") (pinfunction "FB_5") (pintype "input"))
      (node (ref "U$2") (pin "PAD") (pinfunction "AGND_PAD") (pintype "power_in"))
      (node (ref "U$2") (pin "VIA1") (pinfunction "AGND_VIA1") (pintype "power_in"))
      (node (ref "U$2") (pin "VIA2") (pinfunction "AGND_VIA2") (pintype "power_in"))
      (node (ref "U$3") (pin "3") (pinfunction "GND_3") (pintype "power_in"))
      (node (ref "U$4") (pin "1") (pinfunction "PGND_1") (pintype "power_in"))
      (node (ref "U$4") (pin "4") (pinfunction "AGND_4") (pintype "power_in"))
      (node (ref "U$4") (pin "5") (pinfunction "FB_5") (pintype "input"))
      (node (ref "U$4") (pin "PAD") (pinfunction "AGND_PAD") (pintype "power_in"))
      (node (ref "U$4") (pin "VIA1") (pinfunction "AGND_VIA1") (pintype "power_in"))
      (node (ref "U$4") (pin "VIA2") (pinfunction "AGND_VIA2") (pintype "power_in"))
      (node (ref "U$5") (pin "P$12") (pinfunction "GND_P$12") (pintype "power_in"))
      (node (ref "U$5") (pin "P$27") (pinfunction "GND_P$27") (pintype "power_in"))
      (node (ref "U$5") (pin "P$3") (pinfunction "GNDA_P$3") (pintype "power_in"))
      (node (ref "U$5") (pin "P$33") (pinfunction "HIB_P$33") (pintype "input"))
      (node (ref "U$5") (pin "P$35") (pinfunction "GNDX_P$35") (pintype "power_in"))
      (node (ref "U$5") (pin "P$39") (pinfunction "GND_P$39") (pintype "power_in"))
      (node (ref "U$5") (pin "P$55") (pinfunction "GND_P$55") (pintype "power_in"))
      (node (ref "U$6") (pin "4") (pinfunction "4_4") (pintype "bidirectional"))
      (node (ref "U$7") (pin "G1") (pinfunction "CASE_G1") (pintype "power_in"))
      (node (ref "U$7") (pin "G2") (pinfunction "CASE_G2") (pintype "power_in"))
      (node (ref "U$8") (pin "7") (pinfunction "VEE_7") (pintype "power_in"))
      (node (ref "U$8") (pin "8") (pinfunction "GND_8") (pintype "power_in"))
      (node (ref "U$9") (pin "1") (pinfunction "SHDN_1") (pintype "input"))
      (node (ref "U$9") (pin "2") (pinfunction "GND_2") (pintype "power_in"))
      (node (ref "U1") (pin "1") (pinfunction "CLKIN_1") (pintype "bidirectional"))
      (node (ref "U1") (pin "11") (pinfunction "FSYNC_11") (pintype "bidirectional"))
      (node (ref "U1") (pin "15") (pinfunction "GND_15") (pintype "bidirectional"))
      (node (ref "U1") (pin "17") (pinfunction "GND_17") (pintype "bidirectional"))
      (node (ref "U1") (pin "18") (pinfunction "GND_18") (pintype "bidirectional"))
      (node (ref "U1") (pin "9") (pinfunction "AD0_9") (pintype "bidirectional"))
      (node (ref "U2") (pin "6") (pinfunction "GND_6") (pintype "bidirectional"))
      (node (ref "U2") (pin "GND1") (pinfunction "SHIELD_GND1") (pintype "bidirectional"))
      (node (ref "U2") (pin "GND3") (pinfunction "SHIELD_GND3") (pintype "bidirectional"))
    )
    (net (code "13") (name "GPS_EN") (class "Default")
      (node (ref "TP21") (pin "P$1") (pinfunction "1_P$1") (pintype "bidirectional"))
      (node (ref "U$10") (pin "6") (pinfunction "PWR_6") (pintype "input"))
      (node (ref "U$5") (pin "P$7") (pinfunction "PE2_P$7") (pintype "bidirectional"))
    )
    (net (code "14") (name "I2C0_SCL") (class "Default")
      (node (ref "R8") (pin "2") (pinfunction "2_2") (pintype "passive"))
      (node (ref "TP5") (pin "P$1") (pinfunction "1_P$1") (pintype "bidirectional"))
      (node (ref "U$3") (pin "8") (pinfunction "SCL_8") (pintype "bidirectional"))
      (node (ref "U$5") (pin "P$47") (pinfunction "PB2_P$47") (pintype "bidirectional"))
      (node (ref "U1") (pin "23") (pinfunction "SCL_23") (pintype "bidirectional"))
    )
    (net (code "15") (name "I2C0_SDA") (class "Default")
      (node (ref "R7") (pin "2") (pinfunction "2_2") (pintype "passive"))
      (node (ref "TP6") (pin "P$1") (pinfunction "1_P$1") (pintype "bidirectional"))
      (node (ref "U$3") (pin "7") (pinfunction "SDA_7") (pintype "bidirectional"))
      (node (ref "U$5") (pin "P$48") (pinfunction "PB3_P$48") (pintype "bidirectional"))
      (node (ref "U1") (pin "24") (pinfunction "SDA_24") (pintype "bidirectional"))
    )
    (net (code "16") (name "LC") (class "Default")
      (node (ref "U$8") (pin "4") (pinfunction "Y7_4") (pintype "bidirectional"))
      (node (ref "U$9") (pin "6") (pinfunction "OUT_6") (pintype "output"))
    )
    (net (code "17") (name "LOGIC") (class "Default")
      (node (ref "C13") (pin "1") (pinfunction "1_1") (pintype "passive"))
      (node (ref "C27") (pin "1") (pinfunction "1_1") (pintype "passive"))
      (node (ref "R17") (pin "1") (pinfunction "1_1") (pintype "passive"))
      (node (ref "U$2") (pin "2") (pinfunction "VIN_2") (pintype "power_in"))
      (node (ref "U$2") (pin "3") (pinfunction "EN_3") (pintype "input"))
      (node (ref "U$4") (pin "2") (pinfunction "VIN_2") (pintype "power_in"))
      (node (ref "U$4") (pin "3") (pinfunction "EN_3") (pintype "input"))
      (node (ref "U$9") (pin "5") (pinfunction "CS-_5") (pintype "input"))
    )
    (net (code "18") (name "M0_FAULT0") (class "Default")
      (node (ref "U$5") (pin "P$53") (pinfunction "PD6_P$53") (pintype "bidirectional"))
    )
    (net (code "19") (name "M0_PWM0") (class "Default")
      (node (ref "U$18") (pin "5") (pinfunction "A4_5") (pintype "bidirectional"))
      (node (ref "U$5") (pin "P$1") (pinfunction "PB6_P$1") (pintype "bidirectional"))
    )
    (net (code "20") (name "M0_PWM1") (class "Default")
      (node (ref "U$18") (pin "4") (pinfunction "A3_4") (pintype "bidirectional"))
      (node (ref "U$5") (pin "P$4") (pinfunction "PB7_P$4") (pintype "bidirectional"))
    )
    (net (code "21") (name "M0_PWM6") (class "Default")
      (node (ref "U$18") (pin "2") (pinfunction "A1_2") (pintype "bidirectional"))
      (node (ref "U$5") (pin "P$16") (pinfunction "PC4_P$16") (pintype "bidirectional"))
    )
    (net (code "22") (name "M0_PWM7") (class "Default")
      (node (ref "U$18") (pin "3") (pinfunction "A2_3") (pintype "bidirectional"))
      (node (ref "U$5") (pin "P$15") (pinfunction "PC5_P$15") (pintype "bidirectional"))
    )
    (net (code "23") (name "MC1") (class "Default")
      (node (ref "U$1") (pin "P$1") (pinfunction "OUT1_P$1") (pintype "output"))
      (node (ref "U$8") (pin "13") (pinfunction "Y0_13") (pintype "bidirectional"))
    )
    (net (code "24") (name "MC2") (class "Default")
      (node (ref "U$1") (pin "P$7") (pinfunction "OUT2_P$7") (pintype "output"))
      (node (ref "U$8") (pin "14") (pinfunction "Y1_14") (pintype "bidirectional"))
    )
    (net (code "25") (name "MC3") (class "Default")
      (node (ref "U$1") (pin "P$8") (pinfunction "OUT3_P$8") (pintype "output"))
      (node (ref "U$8") (pin "15") (pinfunction "Y2_15") (pintype "bidirectional"))
    )
    (net (code "26") (name "MC4") (class "Default")
      (node (ref "U$1") (pin "P$14") (pinfunction "OUT4_P$14") (pintype "output"))
      (node (ref "U$8") (pin "12") (pinfunction "Y3_12") (pintype "bidirectional"))
    )
    (net (code "27") (name "MPU_INT") (class "Default")
      (node (ref "TP29") (pin "P$1") (pinfunction "1_P$1") (pintype "bidirectional"))
      (node (ref "U$5") (pin "P$30") (pinfunction "PF2_P$30") (pintype "bidirectional"))
      (node (ref "U1") (pin "12") (pinfunction "INT_12") (pintype "bidirectional"))
    )
    (net (code "28") (name "NRF_EN") (class "Default")
      (node (ref "R29") (pin "2") (pinfunction "2_2") (pintype "passive"))
      (node (ref "TP19") (pin "P$1") (pinfunction "1_P$1") (pintype "bidirectional"))
      (node (ref "U$11") (pin "P$1") (pinfunction "CE_P$1") (pintype "input"))
      (node (ref "U$5") (pin "P$60") (pinfunction "PE5_P$60") (pintype "bidirectional"))
    )
    (net (code "29") (name "NRF_IRQ") (class "Default")
      (node (ref "TP18") (pin "P$1") (pinfunction "1_P$1") (pintype "bidirectional"))
      (node (ref "U$11") (pin "P$6") (pinfunction "IRQ_P$6") (pintype "output"))
      (node (ref "U$5") (pin "P$59") (pinfunction "PE4_P$59") (pintype "bidirectional"))
    )
    (net (code "30") (name "Net-(C23-Pad1)") (class "Default")
      (node (ref "C23") (pin "1") (pinfunction "1_1") (pintype "passive"))
      (node (ref "L5") (pin "2") (pinfunction "2_2") (pintype "passive"))
    )
    (net (code "31") (name "Net-(F1-Pad1)") (class "Default")
      (node (ref "F1") (pin "1") (pinfunction "1_1") (pintype "passive"))
      (node (ref "U$6") (pin "1") (pinfunction "1_1") (pintype "bidirectional"))
    )
    (net (code "32") (name "Net-(IC2A-+IN)") (class "Default")
      (node (ref "IC2") (pin "3") (pinfunction "+IN_3") (pintype "input"))
      (node (ref "R11") (pin "2") (pinfunction "2_2") (pintype "passive"))
      (node (ref "R12") (pin "2") (pinfunction "2_2") (pintype "passive"))
    )
    (net (code "33") (name "Net-(IC2A--IN)") (class "Default")
      (node (ref "IC2") (pin "2") (pinfunction "-IN_2") (pintype "input"))
      (node (ref "R13") (pin "2") (pinfunction "2_2") (pintype "passive"))
      (node (ref "R14") (pin "1") (pinfunction "1_1") (pintype "passive"))
    )
    (net (code "34") (name "Net-(IC2B-+IN)") (class "Default")
      (node (ref "IC2") (pin "5") (pinfunction "+IN_5") (pintype "input"))
      (node (ref "R2") (pin "2") (pinfunction "2_2") (pintype "passive"))
      (node (ref "R3") (pin "2") (pinfunction "2_2") (pintype "passive"))
    )
    (net (code "35") (name "Net-(IC2B--IN)") (class "Default")
      (node (ref "IC2") (pin "6") (pinfunction "-IN_6") (pintype "input"))
      (node (ref "R10") (pin "1") (pinfunction "1_1") (pintype "passive"))
      (node (ref "R4") (pin "2") (pinfunction "2_2") (pintype "passive"))
    )
    (net (code "36") (name "Net-(J1-SIGNAL)") (class "Default")
      (node (ref "C23") (pin "2") (pinfunction "2_2") (pintype "passive"))
      (node (ref "C25") (pin "1") (pinfunction "1_1") (pintype "passive"))
      (node (ref "J1") (pin "P$3") (pinfunction "SIGNAL_P$3") (pintype "bidirectional"))
    )
    (net (code "37") (name "Net-(JP5-Pad5)") (class "Default")
      (node (ref "JP5") (pin "5") (pinfunction "5_5") (pintype "passive"))
      (node (ref "RN2") (pin "1") (pinfunction "1_1") (pintype "passive"))
    )
    (net (code "38") (name "Net-(LED1-PadC)") (class "Default")
      (node (ref "LED1") (pin "C") (pinfunction "C_C") (pintype "passive"))
      (node (ref "R6") (pin "1") (pinfunction "1_1") (pintype "passive"))
    )
    (net (code "39") (name "Net-(LED2-PadC)") (class "Default")
      (node (ref "LED2") (pin "C") (pinfunction "C_C") (pintype "passive"))
      (node (ref "R18") (pin "1") (pinfunction "1_1") (pintype "passive"))
    )
    (net (code "40") (name "Net-(LED3-PadC)") (class "Default")
      (node (ref "LED3") (pin "C") (pinfunction "C_C") (pintype "passive"))
      (node (ref "R20") (pin "1") (pinfunction "1_1") (pintype "passive"))
    )
    (net (code "41") (name "Net-(LED4-PadC)") (class "Default")
      (node (ref "LED4") (pin "C") (pinfunction "C_C") (pintype "passive"))
      (node (ref "R31") (pin "1") (pinfunction "1_1") (pintype "passive"))
    )
    (net (code "42") (name "Net-(Q1-D)") (class "Default")
      (node (ref "LED3") (pin "A") (pinfunction "A_A") (pintype "passive"))
      (node (ref "Q1") (pin "3") (pinfunction "D_3") (pintype "passive"))
    )
    (net (code "43") (name "Net-(Q2-D)") (class "Default")
      (node (ref "LED4") (pin "A") (pinfunction "A_A") (pintype "passive"))
      (node (ref "Q2") (pin "3") (pinfunction "D_3") (pintype "passive"))
    )
    (net (code "44") (name "Net-(R5-Pad2)") (class "Default")
      (node (ref "R5") (pin "2") (pinfunction "2_2") (pintype "passive"))
      (node (ref "S1") (pin "1") (pinfunction "1_1") (pintype "passive"))
    )
    (net (code "45") (name "Net-(RN1B-1)") (class "Default")
      (node (ref "JP5") (pin "3") (pinfunction "3_3") (pintype "passive"))
      (node (ref "RN1") (pin "2") (pinfunction "1_2") (pintype "passive"))
      (node (ref "RN2") (pin "3") (pinfunction "1_3") (pintype "passive"))
    )
    (net (code "46") (name "Net-(RN1C-1)") (class "Default")
      (node (ref "JP5") (pin "2") (pinfunction "2_2") (pintype "passive"))
      (node (ref "RN1") (pin "3") (pinfunction "1_3") (pintype "passive"))
      (node (ref "RN2") (pin "4") (pinfunction "1_4") (pintype "passive"))
    )
    (net (code "47") (name "Net-(RN1D-1)") (class "Default")
      (node (ref "JP5") (pin "1") (pinfunction "1_1") (pintype "passive"))
      (node (ref "R25") (pin "1") (pinfunction "1_1") (pintype "passive"))
      (node (ref "RN1") (pin "4") (pinfunction "1_4") (pintype "passive"))
    )
    (net (code "48") (name "Net-(RN2B-1)") (class "Default")
      (node (ref "JP5") (pin "4") (pinfunction "4_4") (pintype "passive"))
      (node (ref "RN1") (pin "1") (pinfunction "1_1") (pintype "passive"))
      (node (ref "RN2") (pin "2") (pinfunction "1_2") (pintype "passive"))
    )
    (net (code "49") (name "Net-(U$2-PG)") (class "Default")
      (node (ref "R1") (pin "2") (pinfunction "2_2") (pintype "passive"))
      (node (ref "U$2") (pin "8") (pinfunction "PG_8") (pintype "input"))
    )
    (net (code "50") (name "Net-(U$2-SW)") (class "Default")
      (node (ref "L1") (pin "1") (pinfunction "1_1") (pintype "passive"))
      (node (ref "U$2") (pin "7") (pinfunction "SW_7") (pintype "output"))
    )
    (net (code "51") (name "Net-(U$3-CAP)") (class "Default")
      (node (ref "C3") (pin "1") (pinfunction "1_1") (pintype "passive"))
      (node (ref "U$3") (pin "2") (pinfunction "CAP_2") (pintype "passive"))
    )
    (net (code "52") (name "Net-(U$4-PG)") (class "Default")
      (node (ref "R9") (pin "2") (pinfunction "2_2") (pintype "passive"))
      (node (ref "U$4") (pin "8") (pinfunction "PG_8") (pintype "input"))
    )
    (net (code "53") (name "Net-(U$4-SW)") (class "Default")
      (node (ref "L6") (pin "1") (pinfunction "1_1") (pintype "passive"))
      (node (ref "U$4") (pin "7") (pinfunction "SW_7") (pintype "output"))
    )
    (net (code "54") (name "Net-(U$5B-OSC0)") (class "Default")
      (node (ref "C40") (pin "2") (pinfunction "2_2") (pintype "passive"))
      (node (ref "U$5") (pin "P$40") (pinfunction "OSC0_P$40") (pintype "bidirectional"))
      (node (ref "U$7") (pin "C1") (pinfunction "C1_C1") (pintype "bidirectional"))
    )
    (net (code "55") (name "Net-(U$5B-OSC1)") (class "Default")
      (node (ref "C41") (pin "2") (pinfunction "2_2") (pintype "passive"))
      (node (ref "U$5") (pin "P$41") (pinfunction "OSC1_P$41") (pintype "bidirectional"))
      (node (ref "U$7") (pin "C2") (pinfunction "C2_C2") (pintype "bidirectional"))
    )
    (net (code "56") (name "Net-(U$11-ANT1)") (class "Default")
      (node (ref "L3") (pin "1") (pinfunction "1_1") (pintype "passive"))
      (node (ref "L4") (pin "2") (pinfunction "2_2") (pintype "passive"))
      (node (ref "U$11") (pin "P$12") (pinfunction "ANT1_P$12") (pintype "passive"))
    )
    (net (code "57") (name "Net-(U$11-ANT2)") (class "Default")
      (node (ref "L3") (pin "2") (pinfunction "2_2") (pintype "passive"))
      (node (ref "L5") (pin "1") (pinfunction "1_1") (pintype "passive"))
      (node (ref "U$11") (pin "P$13") (pinfunction "ANT2_P$13") (pintype "passive"))
    )
    (net (code "58") (name "Net-(U$11-DVDD)") (class "Default")
      (node (ref "C26") (pin "1") (pinfunction "1_1") (pintype "passive"))
      (node (ref "U$11") (pin "P$19") (pinfunction "DVDD_P$19") (pintype "passive"))
    )
    (net (code "59") (name "Net-(U$11-IREF)") (class "Default")
      (node (ref "R21") (pin "2") (pinfunction "2_2") (pintype "passive"))
      (node (ref "U$11") (pin "P$16") (pinfunction "IREF_P$16") (pintype "passive"))
    )
    (net (code "60") (name "Net-(U$11-XC1)") (class "Default")
      (node (ref "C20") (pin "1") (pinfunction "1_1") (pintype "passive"))
      (node (ref "R22") (pin "2") (pinfunction "2_2") (pintype "passive"))
      (node (ref "U$11") (pin "P$10") (pinfunction "XC1_P$10") (pintype "input"))
      (node (ref "U$13") (pin "C2") (pinfunction "C2_C2") (pintype "bidirectional"))
    )
    (net (code "61") (name "Net-(U$11-XC2)") (class "Default")
      (node (ref "C19") (pin "1") (pinfunction "1_1") (pintype "passive"))
      (node (ref "R22") (pin "1") (pinfunction "1_1") (pintype "passive"))
      (node (ref "U$11") (pin "P$9") (pinfunction "XC2_P$9") (pintype "output"))
      (node (ref "U$13") (pin "C1") (pinfunction "C1_C1") (pintype "bidirectional"))
    )
    (net (code "62") (name "Net-(U$12-C1)") (class "Default")
      (node (ref "C18") (pin "1") (pinfunction "1_1") (pintype "passive"))
      (node (ref "U$12") (pin "1") (pinfunction "C1_1") (pintype "bidirectional"))
      (node (ref "U$5") (pin "P$36") (pinfunction "XOSC1_P$36") (pintype "bidirectional"))
    )
    (net (code "63") (name "Net-(U$12-C2)") (class "Default")
      (node (ref "C17") (pin "1") (pinfunction "1_1") (pintype "passive"))
      (node (ref "U$12") (pin "2") (pinfunction "C2_2") (pintype "bidirectional"))
      (node (ref "U$5") (pin "P$34") (pinfunction "XOSC0_P$34") (pintype "bidirectional"))
    )
    (net (code "64") (name "Net-(U1-CPOUT)") (class "Default")
      (node (ref "C12") (pin "1") (pinfunction "1_1") (pintype "passive"))
      (node (ref "U1") (pin "20") (pinfunction "CPOUT_20") (pintype "bidirectional"))
    )
    (net (code "65") (name "Net-(U1-REGOUT)") (class "Default")
      (node (ref "C11") (pin "1") (pinfunction "1_1") (pintype "passive"))
      (node (ref "U1") (pin "10") (pinfunction "REGOUT_10") (pintype "bidirectional"))
    )
    (net (code "66") (name "OE") (class "Default")
      (node (ref "R30") (pin "1") (pinfunction "1_1") (pintype "passive"))
      (node (ref "TP24") (pin "P$1") (pinfunction "1_P$1") (pintype "bidirectional"))
      (node (ref "U$18") (pin "8") (pinfunction "OE_8") (pintype "input"))
      (node (ref "U$5") (pin "P$17") (pinfunction "PA0_P$17") (pintype "bidirectional"))
      (node (ref "U$8") (pin "6") (pinfunction "E_6") (pintype "input"))
    )
    (net (code "67") (name "PA1") (class "Default")
      (node (ref "TP25") (pin "P$1") (pinfunction "1_P$1") (pintype "bidirectional"))
      (node (ref "U$5") (pin "P$18") (pinfunction "PA1_P$18") (pintype "bidirectional"))
    )
    (net (code "68") (name "PB4") (class "Default")
      (node (ref "U$5") (pin "P$58") (pinfunction "PB4_P$58") (pintype "bidirectional"))
    )
    (net (code "69") (name "PB5") (class "Default")
      (node (ref "U$5") (pin "P$57") (pinfunction "PB5_P$57") (pintype "bidirectional"))
    )
    (net (code "70") (name "PC6") (class "Default")
      (node (ref "U$5") (pin "P$14") (pinfunction "PC6_P$14") (pintype "bidirectional"))
    )
    (net (code "71") (name "PC7") (class "Default")
      (node (ref "TP27") (pin "P$1") (pinfunction "1_P$1") (pintype "bidirectional"))
      (node (ref "U$5") (pin "P$13") (pinfunction "PC7_P$13") (pintype "bidirectional"))
    )
    (net (code "72") (name "PD7") (class "Default")
      (node (ref "U$5") (pin "P$10") (pinfunction "PD7_P$10") (pintype "bidirectional"))
    )
    (net (code "73") (name "PF1") (class "Default")
      (node (ref "U$5") (pin "P$29") (pinfunction "PF1_P$29") (pintype "bidirectional"))
    )
    (net (code "74") (name "PF4") (class "Default")
      (node (ref "U$5") (pin "P$5") (pinfunction "PF4_P$5") (pintype "bidirectional"))
    )
    (net (code "75") (name "PWM0") (class "Default")
      (node (ref "JP1") (pin "11") (pinfunction "11_11") (pintype "passive"))
      (node (ref "U$18") (pin "10") (pinfunction "B4_10") (pintype "bidirectional"))
    )
    (net (code "76") (name "PWM1") (class "Default")
      (node (ref "JP1") (pin "12") (pinfunction "12_12") (pintype "passive"))
      (node (ref "U$18") (pin "11") (pinfunction "B3_11") (pintype "bidirectional"))
    )
    (net (code "77") (name "PWM2") (class "Default")
      (node (ref "JP1") (pin "1") (pinfunction "1_1") (pintype "passive"))
      (node (ref "U$18") (pin "13") (pinfunction "B1_13") (pintype "bidirectional"))
    )
    (net (code "78") (name "PWM3") (class "Default")
      (node (ref "JP1") (pin "2") (pinfunction "2_2") (pintype "passive"))
      (node (ref "U$18") (pin "12") (pinfunction "B2_12") (pintype "bidirectional"))
    )
    (net (code "79") (name "RS1+") (class "Default")
      (node (ref "C6") (pin "1") (pinfunction "1_1") (pintype "passive"))
      (node (ref "JP2") (pin "5") (pinfunction "5_5") (pintype "passive"))
      (node (ref "U$1") (pin "P$3") (pinfunction "RS1+_P$3") (pintype "passive"))
    )
    (net (code "80") (name "RS1-") (class "Default")
      (node (ref "C6") (pin "2") (pinfunction "2_2") (pintype "passive"))
      (node (ref "JP2") (pin "7") (pinfunction "7_7") (pintype "passive"))
      (node (ref "U$1") (pin "P$2") (pinfunction "RS1-_P$2") (pintype "passive"))
    )
    (net (code "81") (name "RS2+") (class "Default")
      (node (ref "C5") (pin "1") (pinfunction "1_1") (pintype "passive"))
      (node (ref "JP2") (pin "3") (pinfunction "3_3") (pintype "passive"))
      (node (ref "U$1") (pin "P$5") (pinfunction "RS2+_P$5") (pintype "passive"))
    )
    (net (code "82") (name "RS2-") (class "Default")
      (node (ref "C5") (pin "2") (pinfunction "2_2") (pintype "passive"))
      (node (ref "JP2") (pin "1") (pinfunction "1_1") (pintype "passive"))
      (node (ref "U$1") (pin "P$6") (pinfunction "RS2-_P$6") (pintype "passive"))
    )
    (net (code "83") (name "RS3+") (class "Default")
      (node (ref "C7") (pin "2") (pinfunction "2_2") (pintype "passive"))
      (node (ref "JP2") (pin "4") (pinfunction "4_4") (pintype "passive"))
      (node (ref "U$1") (pin "P$10") (pinfunction "RS3+_P$10") (pintype "passive"))
    )
    (net (code "84") (name "RS3-") (class "Default")
      (node (ref "C7") (pin "1") (pinfunction "1_1") (pintype "passive"))
      (node (ref "JP2") (pin "2") (pinfunction "2_2") (pintype "passive"))
      (node (ref "U$1") (pin "P$9") (pinfunction "RS3-_P$9") (pintype "passive"))
    )
    (net (code "85") (name "RS4+") (class "Default")
      (node (ref "C8") (pin "2") (pinfunction "2_2") (pintype "passive"))
      (node (ref "JP2") (pin "6") (pinfunction "6_6") (pintype "passive"))
      (node (ref "U$1") (pin "P$12") (pinfunction "RS4+_P$12") (pintype "passive"))
    )
    (net (code "86") (name "RS4-") (class "Default")
      (node (ref "C8") (pin "1") (pinfunction "1_1") (pintype "passive"))
      (node (ref "JP2") (pin "8") (pinfunction "8_8") (pintype "passive"))
      (node (ref "U$1") (pin "P$13") (pinfunction "RS4-_P$13") (pintype "passive"))
    )
    (net (code "87") (name "RST") (class "Default")
      (node (ref "C42") (pin "1") (pinfunction "1_1") (pintype "passive"))
      (node (ref "R24") (pin "1") (pinfunction "1_1") (pintype "passive"))
      (node (ref "R5") (pin "1") (pinfunction "1_1") (pintype "passive"))
      (node (ref "SJ1") (pin "2") (pinfunction "2_2") (pintype "passive"))
      (node (ref "U$5") (pin "P$38") (pinfunction "RST_P$38") (pintype "input"))
    )
    (net (code "88") (name "S0") (class "Default")
      (node (ref "TP12") (pin "P$1") (pinfunction "1_P$1") (pintype "bidirectional"))
      (node (ref "U$5") (pin "P$23") (pinfunction "PA6_P$23") (pintype "bidirectional"))
      (node (ref "U$8") (pin "11") (pinfunction "S0_11") (pintype "input"))
    )
    (net (code "89") (name "S1") (class "Default")
      (node (ref "TP10") (pin "P$1") (pinfunction "1_P$1") (pintype "bidirectional"))
      (node (ref "U$5") (pin "P$28") (pinfunction "PF0_P$28") (pintype "bidirectional"))
      (node (ref "U$8") (pin "10") (pinfunction "S1_10") (pintype "input"))
    )
    (net (code "90") (name "S2") (class "Default")
      (node (ref "TP13") (pin "P$1") (pinfunction "1_P$1") (pintype "bidirectional"))
      (node (ref "U$5") (pin "P$24") (pinfunction "PA7_P$24") (pintype "bidirectional"))
      (node (ref "U$8") (pin "9") (pinfunction "S2_9") (pintype "input"))
    )
    (net (code "91") (name "SD_PRES") (class "Default")
      (node (ref "R19") (pin "1") (pinfunction "1_1") (pintype "passive"))
      (node (ref "TP20") (pin "P$1") (pinfunction "1_P$1") (pintype "bidirectional"))
      (node (ref "U$5") (pin "P$31") (pinfunction "PF3_P$31") (pintype "bidirectional"))
      (node (ref "U2") (pin "CD1") (pinfunction "SHIELD_CD1") (pintype "bidirectional"))
      (node (ref "U2") (pin "CD2") (pinfunction "SHIELD_CD2") (pintype "bidirectional"))
    )
    (net (code "92") (name "SPI0_MISO") (class "Default")
      (node (ref "R27") (pin "1") (pinfunction "1_1") (pintype "passive"))
      (node (ref "TP3") (pin "P$1") (pinfunction "1_P$1") (pintype "bidirectional"))
      (node (ref "U$5") (pin "P$21") (pinfunction "PA4_P$21") (pintype "bidirectional"))
      (node (ref "U2") (pin "7") (pinfunction "DO_7") (pintype "bidirectional"))
    )
    (net (code "93") (name "SPI0_MOSI") (class "Default")
      (node (ref "TP4") (pin "P$1") (pinfunction "1_P$1") (pintype "bidirectional"))
      (node (ref "U$5") (pin "P$22") (pinfunction "PA5_P$22") (pintype "bidirectional"))
      (node (ref "U2") (pin "3") (pinfunction "DI_3") (pintype "bidirectional"))
    )
    (net (code "94") (name "SPI0_SCK") (class "Default")
      (node (ref "TP1") (pin "P$1") (pinfunction "1_P$1") (pintype "bidirectional"))
      (node (ref "U$5") (pin "P$19") (pinfunction "PA2_P$19") (pintype "bidirectional"))
      (node (ref "U2") (pin "5") (pinfunction "SCK_5") (pintype "bidirectional"))
    )
    (net (code "95") (name "SPI0_SS") (class "Default")
      (node (ref "Q1") (pin "1") (pinfunction "G_1") (pintype "passive"))
      (node (ref "R23") (pin "1") (pinfunction "1_1") (pintype "passive"))
      (node (ref "TP2") (pin "P$1") (pinfunction "1_P$1") (pintype "bidirectional"))
      (node (ref "U$5") (pin "P$20") (pinfunction "PA3_P$20") (pintype "bidirectional"))
      (node (ref "U2") (pin "2") (pinfunction "CS_2") (pintype "bidirectional"))
    )
    (net (code "96") (name "SPI1_MISO") (class "Default")
      (node (ref "R28") (pin "1") (pinfunction "1_1") (pintype "passive"))
      (node (ref "TP9") (pin "P$1") (pinfunction "1_P$1") (pintype "bidirectional"))
      (node (ref "U$11") (pin "P$5") (pinfunction "MISO_P$5") (pintype "output"))
      (node (ref "U$5") (pin "P$63") (pinfunction "PD2_P$63") (pintype "bidirectional"))
    )
    (net (code "97") (name "SPI1_MOSI") (class "Default")
      (node (ref "TP17") (pin "P$1") (pinfunction "1_P$1") (pintype "bidirectional"))
      (node (ref "U$11") (pin "P$4") (pinfunction "MOSI_P$4") (pintype "input"))
      (node (ref "U$5") (pin "P$64") (pinfunction "PD3_P$64") (pintype "bidirectional"))
    )
    (net (code "98") (name "SPI1_SCK") (class "Default")
      (node (ref "TP7") (pin "P$1") (pinfunction "1_P$1") (pintype "bidirectional"))
      (node (ref "U$11") (pin "P$3") (pinfunction "SCK_P$3") (pintype "input"))
      (node (ref "U$5") (pin "P$61") (pinfunction "PD0_P$61") (pintype "bidirectional"))
    )
    (net (code "99") (name "SPI1_SS") (class "Default")
      (node (ref "Q2") (pin "1") (pinfunction "G_1") (pintype "passive"))
      (node (ref "R26") (pin "1") (pinfunction "1_1") (pintype "passive"))
      (node (ref "TP8") (pin "P$1") (pinfunction "1_P$1") (pintype "bidirectional"))
      (node (ref "U$11") (pin "P$2") (pinfunction "CS_P$2") (pintype "input"))
      (node (ref "U$5") (pin "P$62") (pinfunction "PD1_P$62") (pintype "bidirectional"))
    )
    (net (code "100") (name "TCK") (class "Default")
      (node (ref "RN2") (pin "5") (pinfunction "2_5") (pintype "passive"))
      (node (ref "U$5") (pin "P$52") (pinfunction "PC0_P$52") (pintype "bidirectional"))
    )
    (net (code "101") (name "TDI") (class "Default")
      (node (ref "RN2") (pin "7") (pinfunction "2_7") (pintype "passive"))
      (node (ref "U$5") (pin "P$50") (pinfunction "PC2_P$50") (pintype "bidirectional"))
    )
    (net (code "102") (name "TDO") (class "Default")
      (node (ref "RN2") (pin "8") (pinfunction "2_8") (pintype "passive"))
      (node (ref "U$5") (pin "P$49") (pinfunction "PC3_P$49") (pintype "bidirectional"))
    )
    (net (code "103") (name "TMS") (class "Default")
      (node (ref "RN2") (pin "6") (pinfunction "2_6") (pintype "passive"))
      (node (ref "U$5") (pin "P$51") (pinfunction "PC1_P$51") (pintype "bidirectional"))
    )
    (net (code "104") (name "TRST") (class "Default")
      (node (ref "R25") (pin "2") (pinfunction "2_2") (pintype "passive"))
      (node (ref "SJ1") (pin "1") (pinfunction "1_1") (pintype "passive"))
    )
    (net (code "105") (name "UART7_RX") (class "Default")
      (node (ref "TP23") (pin "P$1") (pinfunction "1_P$1") (pintype "bidirectional"))
      (node (ref "U$10") (pin "3") (pinfunction "TXA_3") (pintype "output"))
      (node (ref "U$5") (pin "P$9") (pinfunction "PE0_P$9") (pintype "bidirectional"))
    )
    (net (code "106") (name "UART7_TX") (class "Default")
      (node (ref "TP22") (pin "P$1") (pinfunction "1_P$1") (pintype "bidirectional"))
      (node (ref "U$10") (pin "4") (pinfunction "RXA_4") (pintype "input"))
      (node (ref "U$5") (pin "P$8") (pinfunction "PE1_P$8") (pintype "bidirectional"))
    )
    (net (code "107") (name "USB0_D_N") (class "Default")
      (node (ref "U$5") (pin "P$43") (pinfunction "PD4_P$43") (pintype "bidirectional"))
    )
    (net (code "108") (name "USB0_D_P") (class "Default")
      (node (ref "U$5") (pin "P$44") (pinfunction "PD5_P$44") (pintype "bidirectional"))
    )
    (net (code "109") (name "USB0_ID") (class "Default")
      (node (ref "U$5") (pin "P$45") (pinfunction "PB0_P$45") (pintype "bidirectional"))
    )
    (net (code "110") (name "USB0_VBUS") (class "Default")
      (node (ref "U$5") (pin "P$46") (pinfunction "PB1_P$46") (pintype "bidirectional"))
    )
    (net (code "111") (name "VCC-ISO") (class "Default")
      (node (ref "C30") (pin "1") (pinfunction "1_1") (pintype "passive"))
      (node (ref "C43") (pin "1") (pinfunction "1_1") (pintype "passive"))
      (node (ref "L7") (pin "2") (pinfunction "2_2") (pintype "passive"))
      (node (ref "U$11") (pin "P$15") (pinfunction "VDD_P$15") (pintype "power_in"))
      (node (ref "U$11") (pin "P$18") (pinfunction "VDD_P$18") (pintype "power_in"))
      (node (ref "U$11") (pin "P$7") (pinfunction "VDD_P$7") (pintype "power_in"))
    )
    (net (code "112") (name "VDDC") (class "Default")
      (node (ref "C46") (pin "1") (pinfunction "1_1") (pintype "passive"))
      (node (ref "C47") (pin "1") (pinfunction "1_1") (pintype "passive"))
      (node (ref "C51") (pin "1") (pinfunction "1_1") (pintype "passive"))
      (node (ref "C52") (pin "1") (pinfunction "1_1") (pintype "passive"))
      (node (ref "U$5") (pin "P$25") (pinfunction "VDDC_P$25") (pintype "power_in"))
      (node (ref "U$5") (pin "P$56") (pinfunction "VDDC_P$56") (pintype "power_in"))
    )
    (net (code "113") (name "VDD_PA") (class "Default")
      (node (ref "C21") (pin "1") (pinfunction "1_1") (pintype "passive"))
      (node (ref "C22") (pin "1") (pinfunction "1_1") (pintype "passive"))
      (node (ref "L4") (pin "1") (pinfunction "1_1") (pintype "passive"))
      (node (ref "U$11") (pin "P$11") (pinfunction "VDD_PA_P$11") (pintype "output"))
    )
    (net (code "114") (name "V_BATT") (class "Default")
      (node (ref "C24") (pin "1") (pinfunction "1_1") (pintype "passive"))
      (node (ref "C37") (pin "1") (pinfunction "1_1") (pintype "passive"))
      (node (ref "F1") (pin "2") (pinfunction "2_2") (pintype "passive"))
      (node (ref "IC2") (pin "8") (pinfunction "V+_8") (pintype "power_in"))
      (node (ref "R17") (pin "2") (pinfunction "2_2") (pintype "passive"))
      (node (ref "R2") (pin "1") (pinfunction "1_1") (pintype "passive"))
      (node (ref "U$9") (pin "3") (pinfunction "VCC_3") (pintype "power_in"))
      (node (ref "U$9") (pin "4") (pinfunction "CS+_4") (pintype "input"))
    )
    (net (code "115") (name "WAKE") (class "Default")
      (node (ref "R32") (pin "2") (pinfunction "2_2") (pintype "passive"))
      (node (ref "TP26") (pin "P$1") (pinfunction "1_P$1") (pintype "bidirectional"))
      (node (ref "U$5") (pin "P$32") (pinfunction "WAKE_P$32") (pintype "bidirectional"))
    )
    (net (code "116") (name "unconnected-(U$3-INT1-Pad6)") (class "Default")
      (node (ref "U$3") (pin "6") (pinfunction "INT1_6") (pintype "output"))
    )
    (net (code "117") (name "unconnected-(U$3-INT2-Pad5)") (class "Default")
      (node (ref "U$3") (pin "5") (pinfunction "INT2_5") (pintype "output"))
    )
    (net (code "118") (name "unconnected-(U1-CLKOUT-Pad22)") (class "Default")
      (node (ref "U1") (pin "22") (pinfunction "CLKOUT_22") (pintype "bidirectional"))
    )
    (net (code "119") (name "unconnected-(U1-E_SCL-Pad7)") (class "Default")
      (node (ref "U1") (pin "7") (pinfunction "E_SCL_7") (pintype "bidirectional"))
    )
    (net (code "120") (name "unconnected-(U1-E_SDA-Pad6)") (class "Default")
      (node (ref "U1") (pin "6") (pinfunction "E_SDA_6") (pintype "bidirectional"))
    )
    (net (code "121") (name "unconnected-(U2-NC-Pad1)") (class "Default")
      (node (ref "U2") (pin "1") (pinfunction "NC_1") (pintype "bidirectional"))
    )
    (net (code "122") (name "unconnected-(U2-RSV-Pad8)") (class "Default")
      (node (ref "U2") (pin "8") (pinfunction "RSV_8") (pintype "bidirectional"))
    )
  )
)
